# axiom_beta_sensor_cmv12000_tht_v0_16_r1_.net
KiCad netlist of a schematic drawn in EAGLE
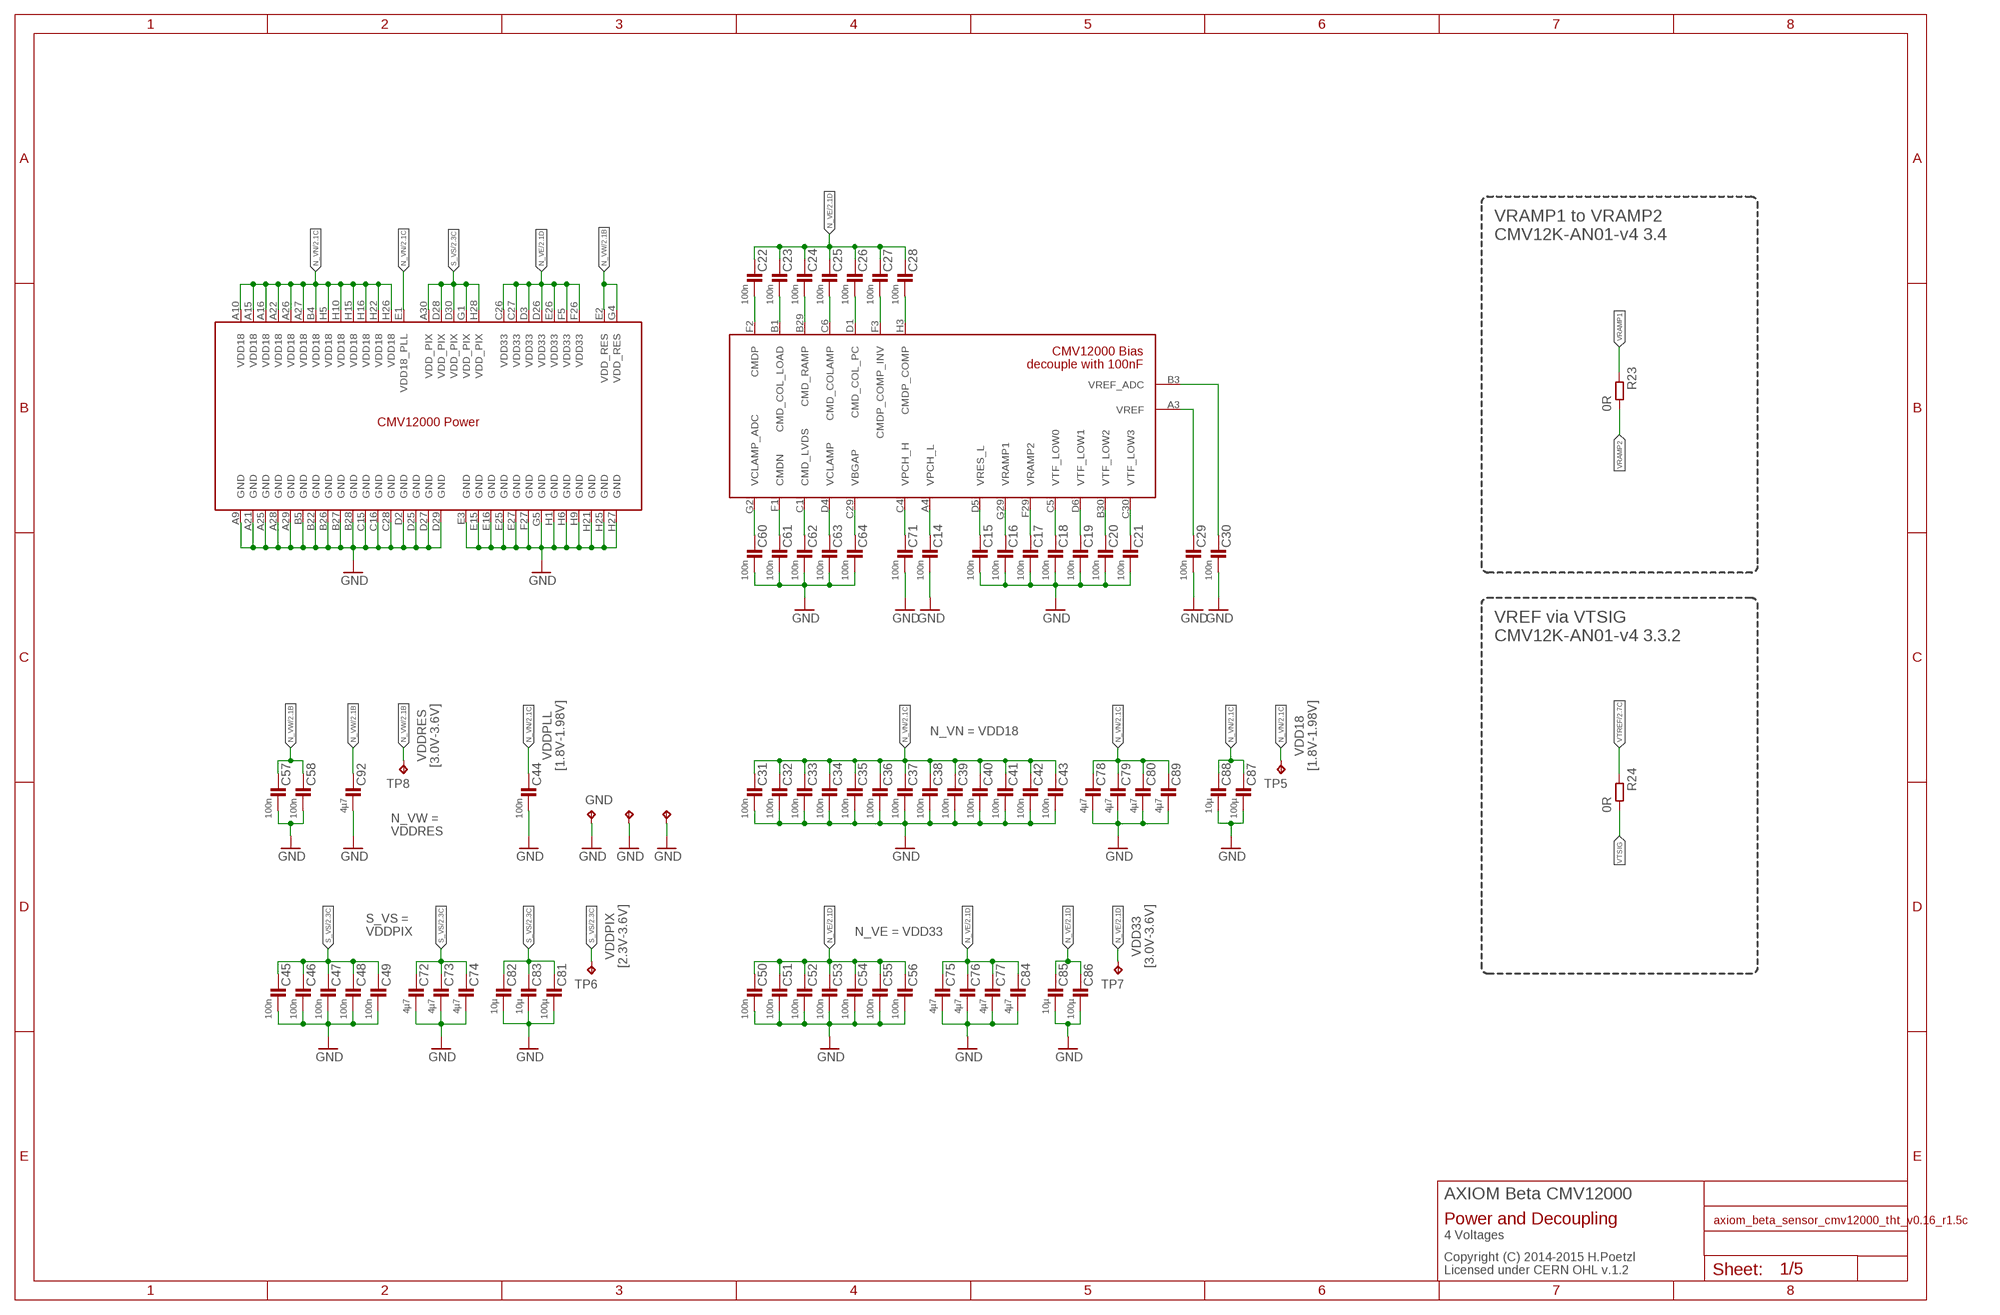
[diagram p0: schematic, sheet 1]
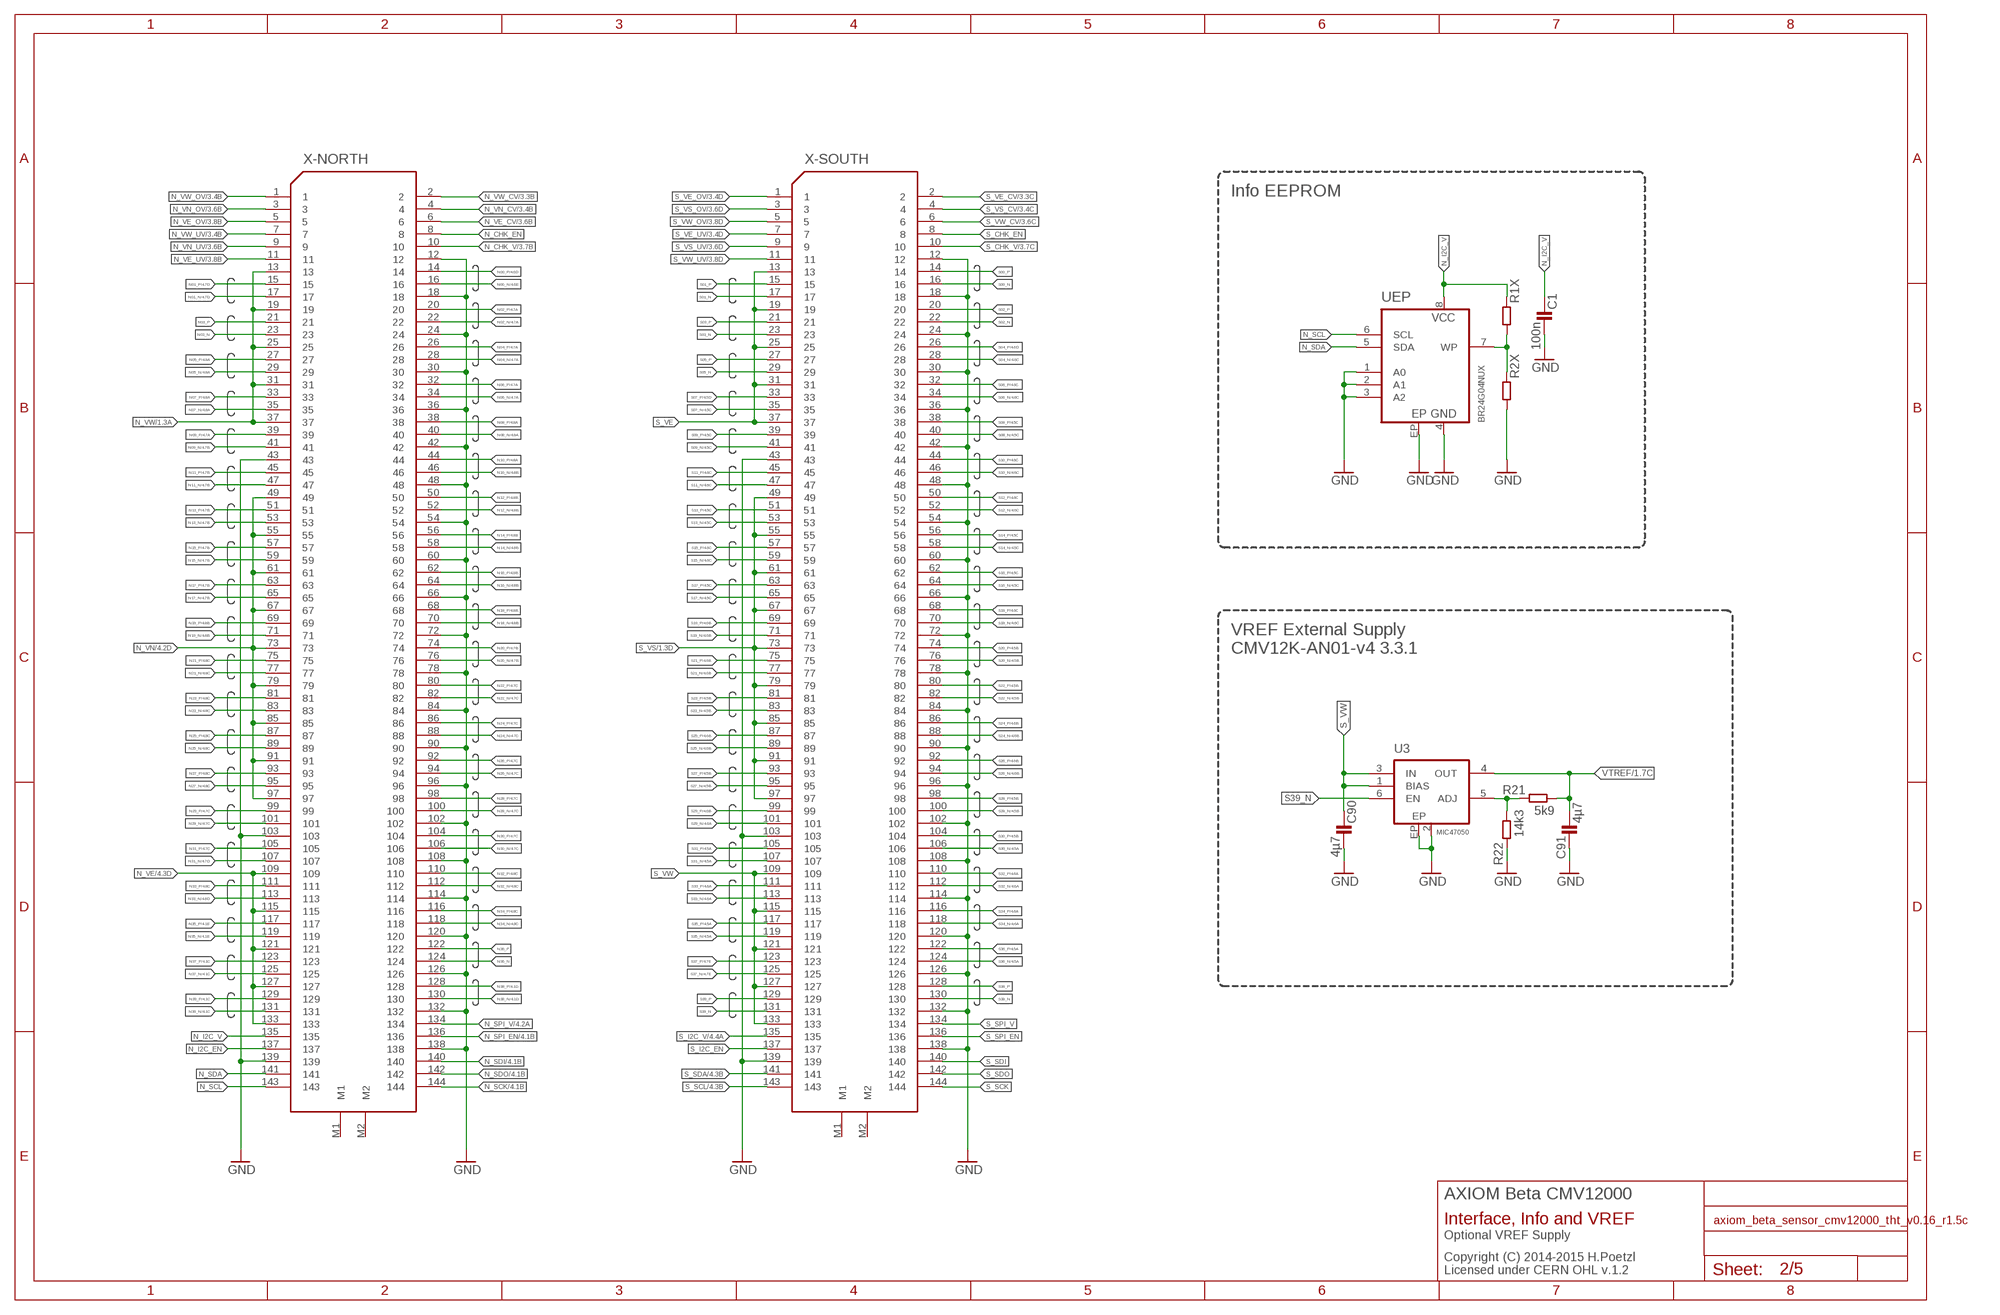
[diagram p1: schematic, sheet 2]
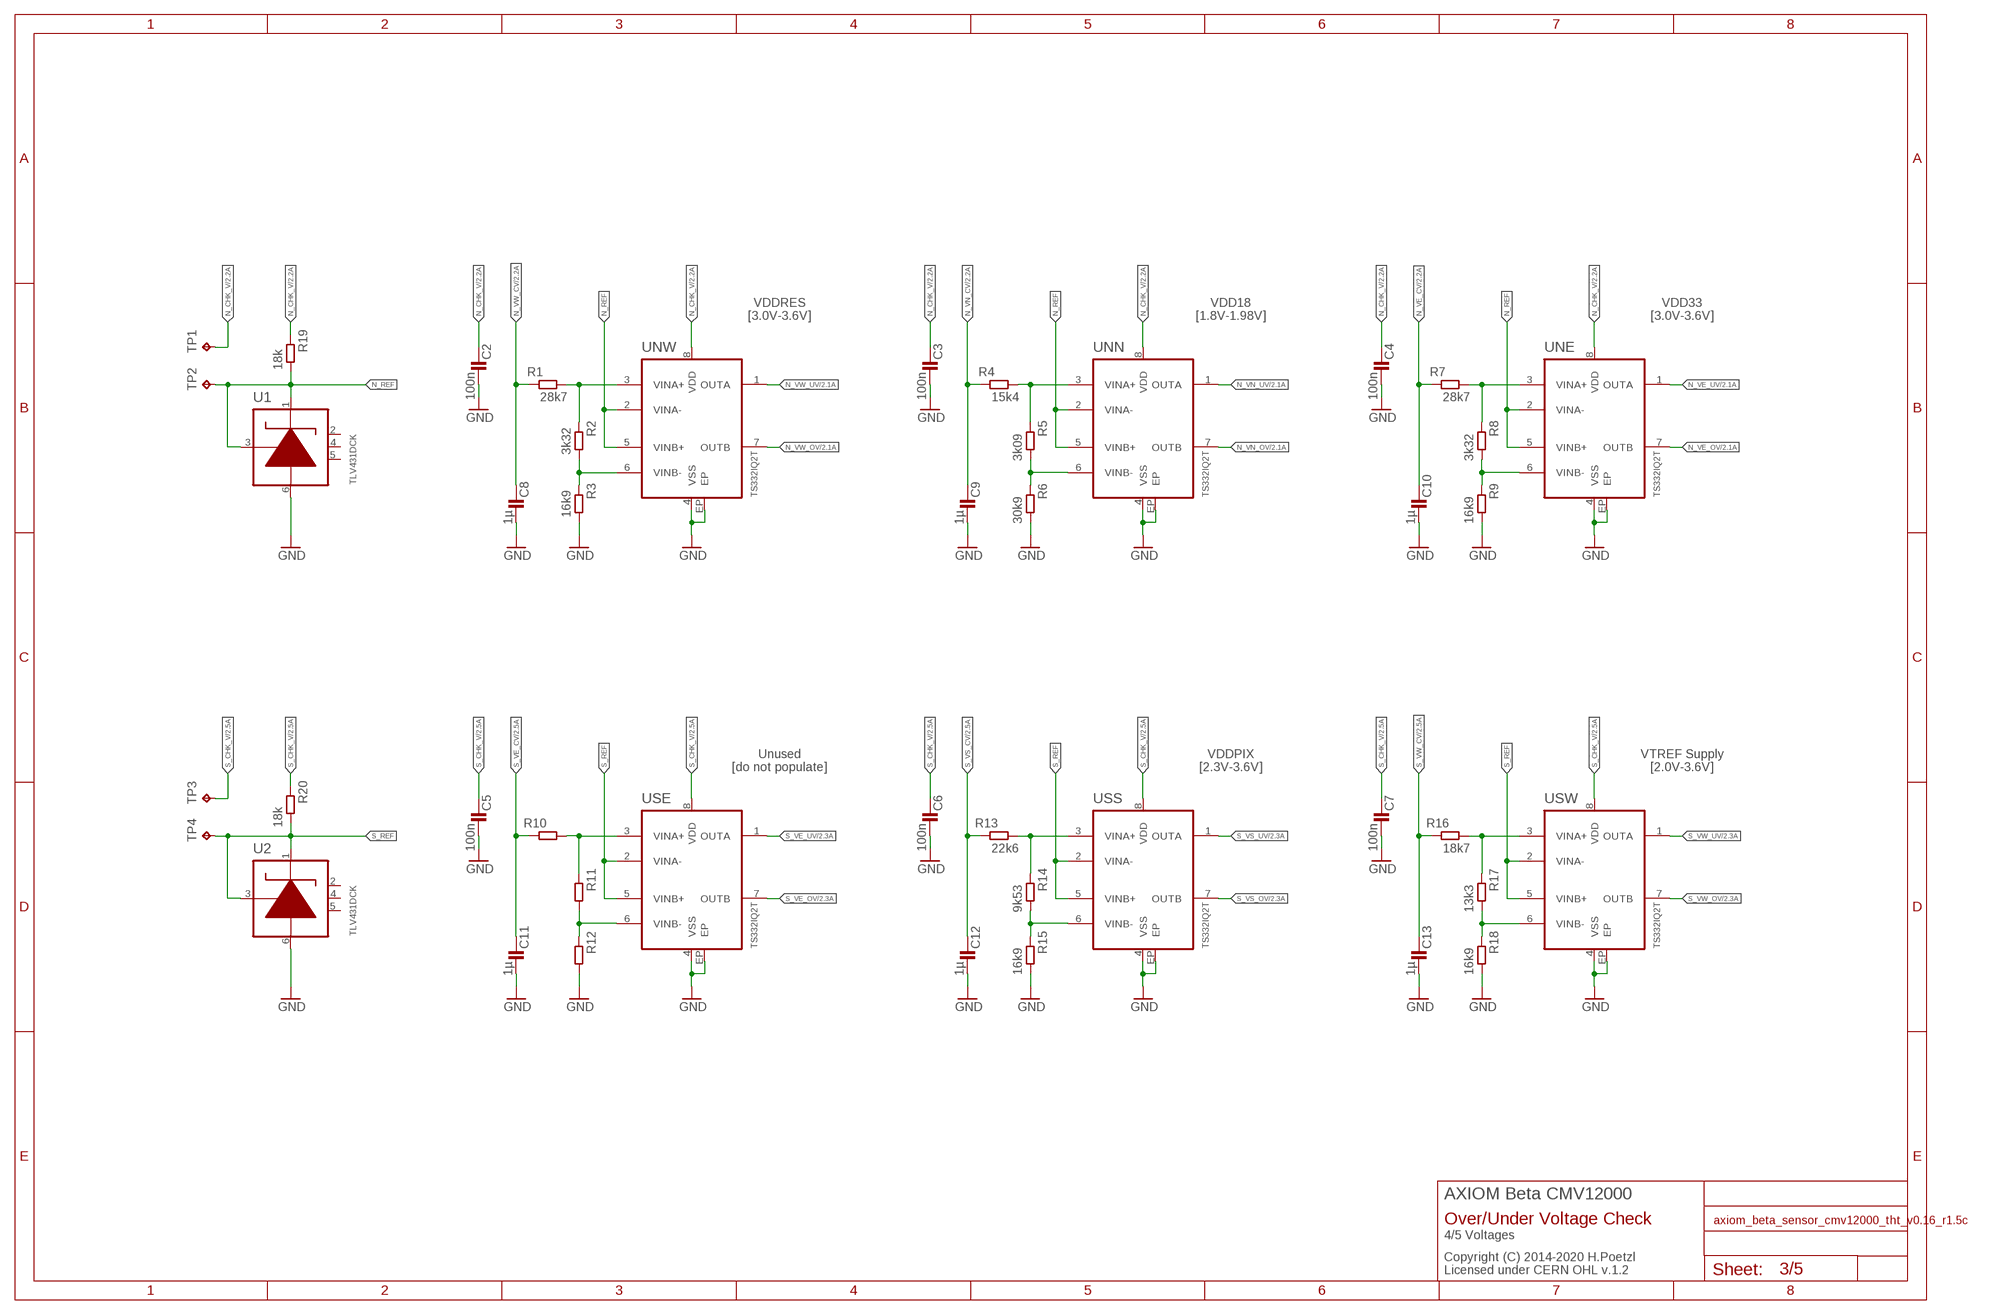
[diagram p2: schematic, sheet 3]
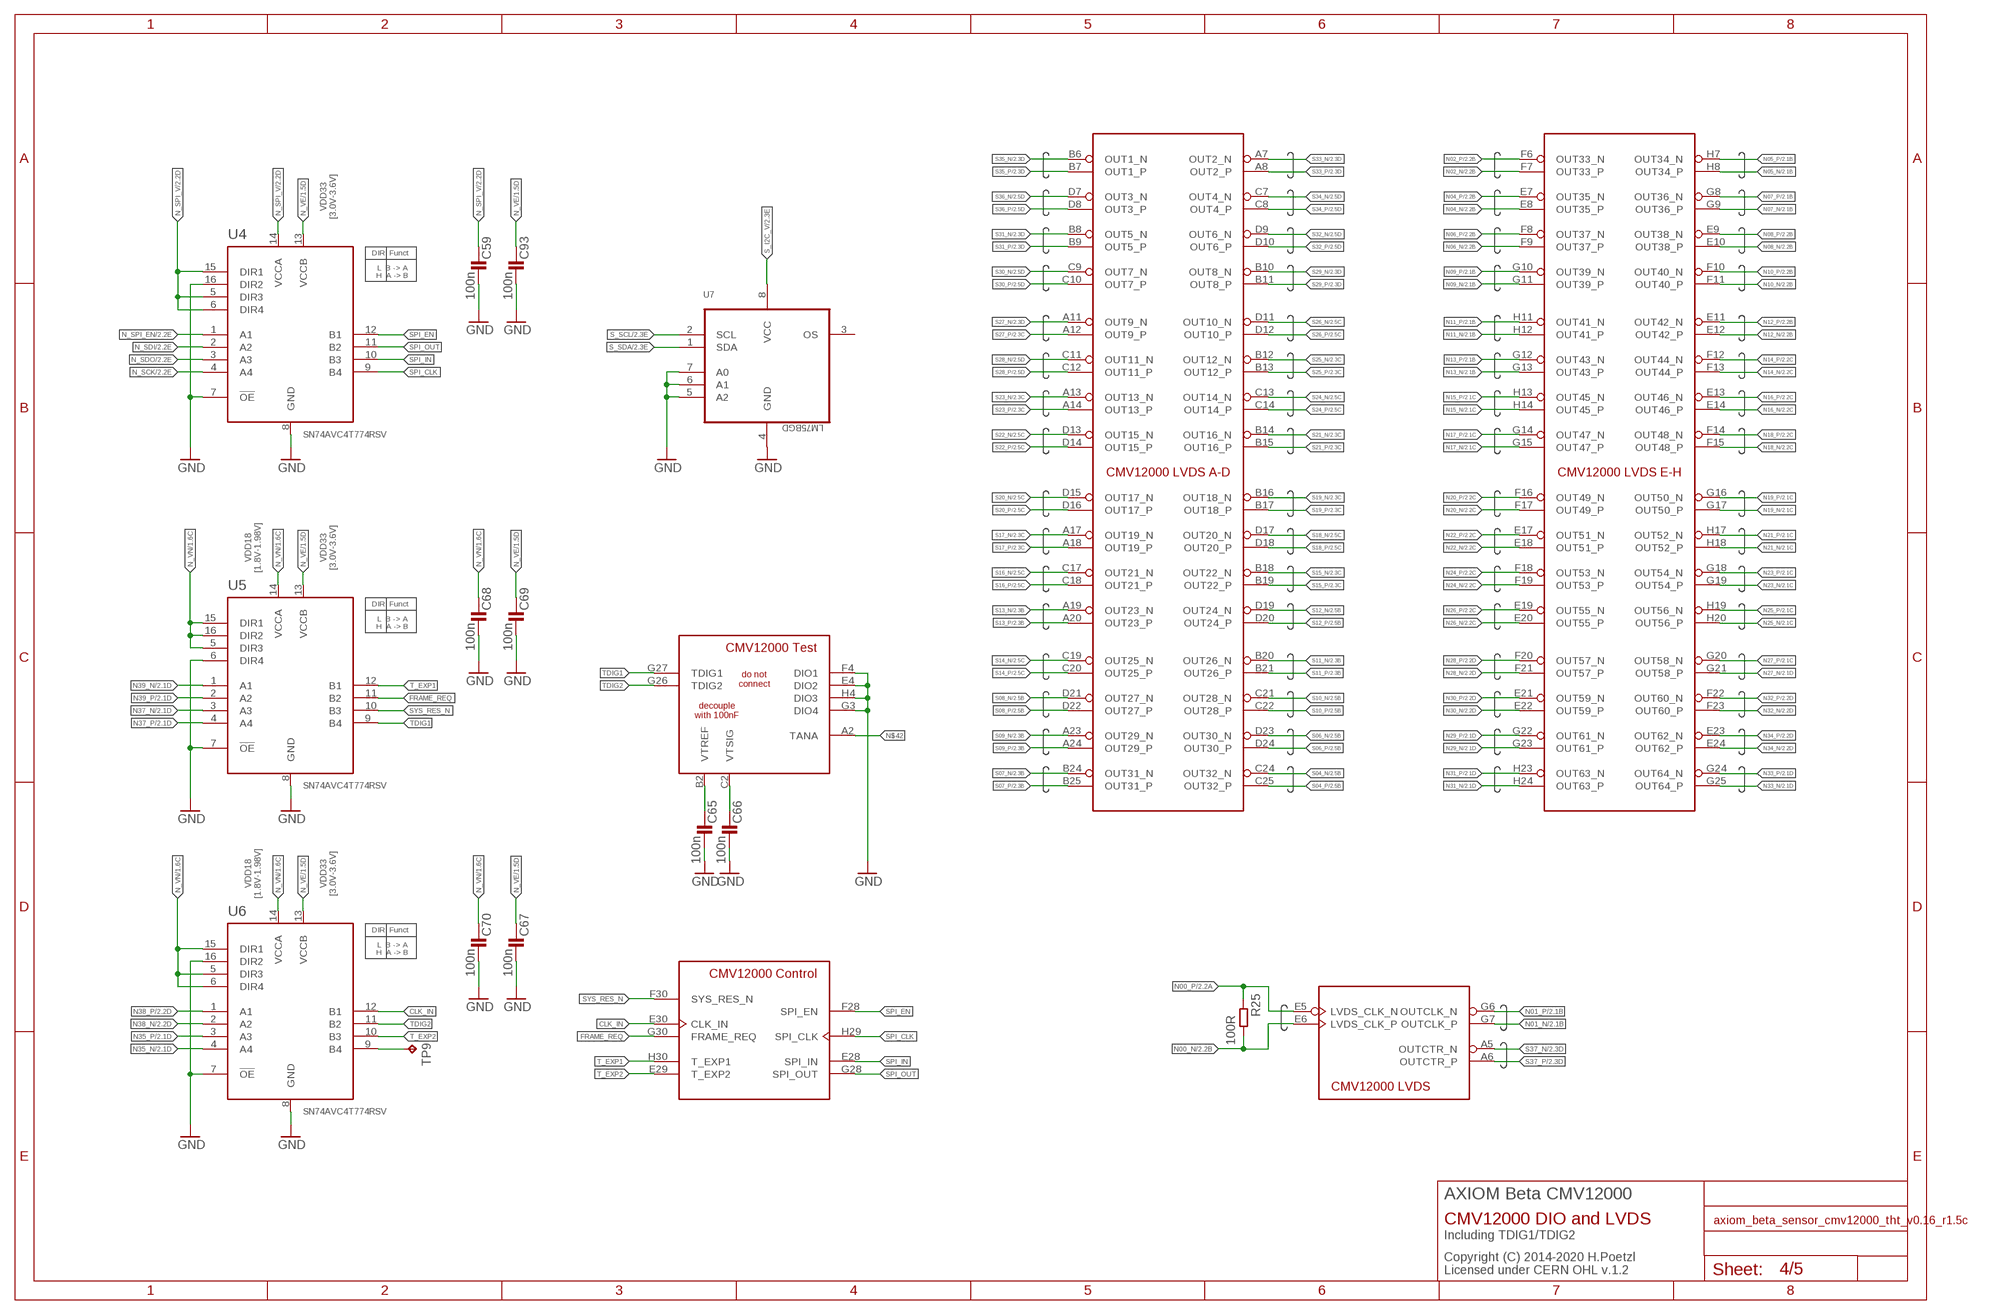
[diagram p3: schematic, sheet 4]
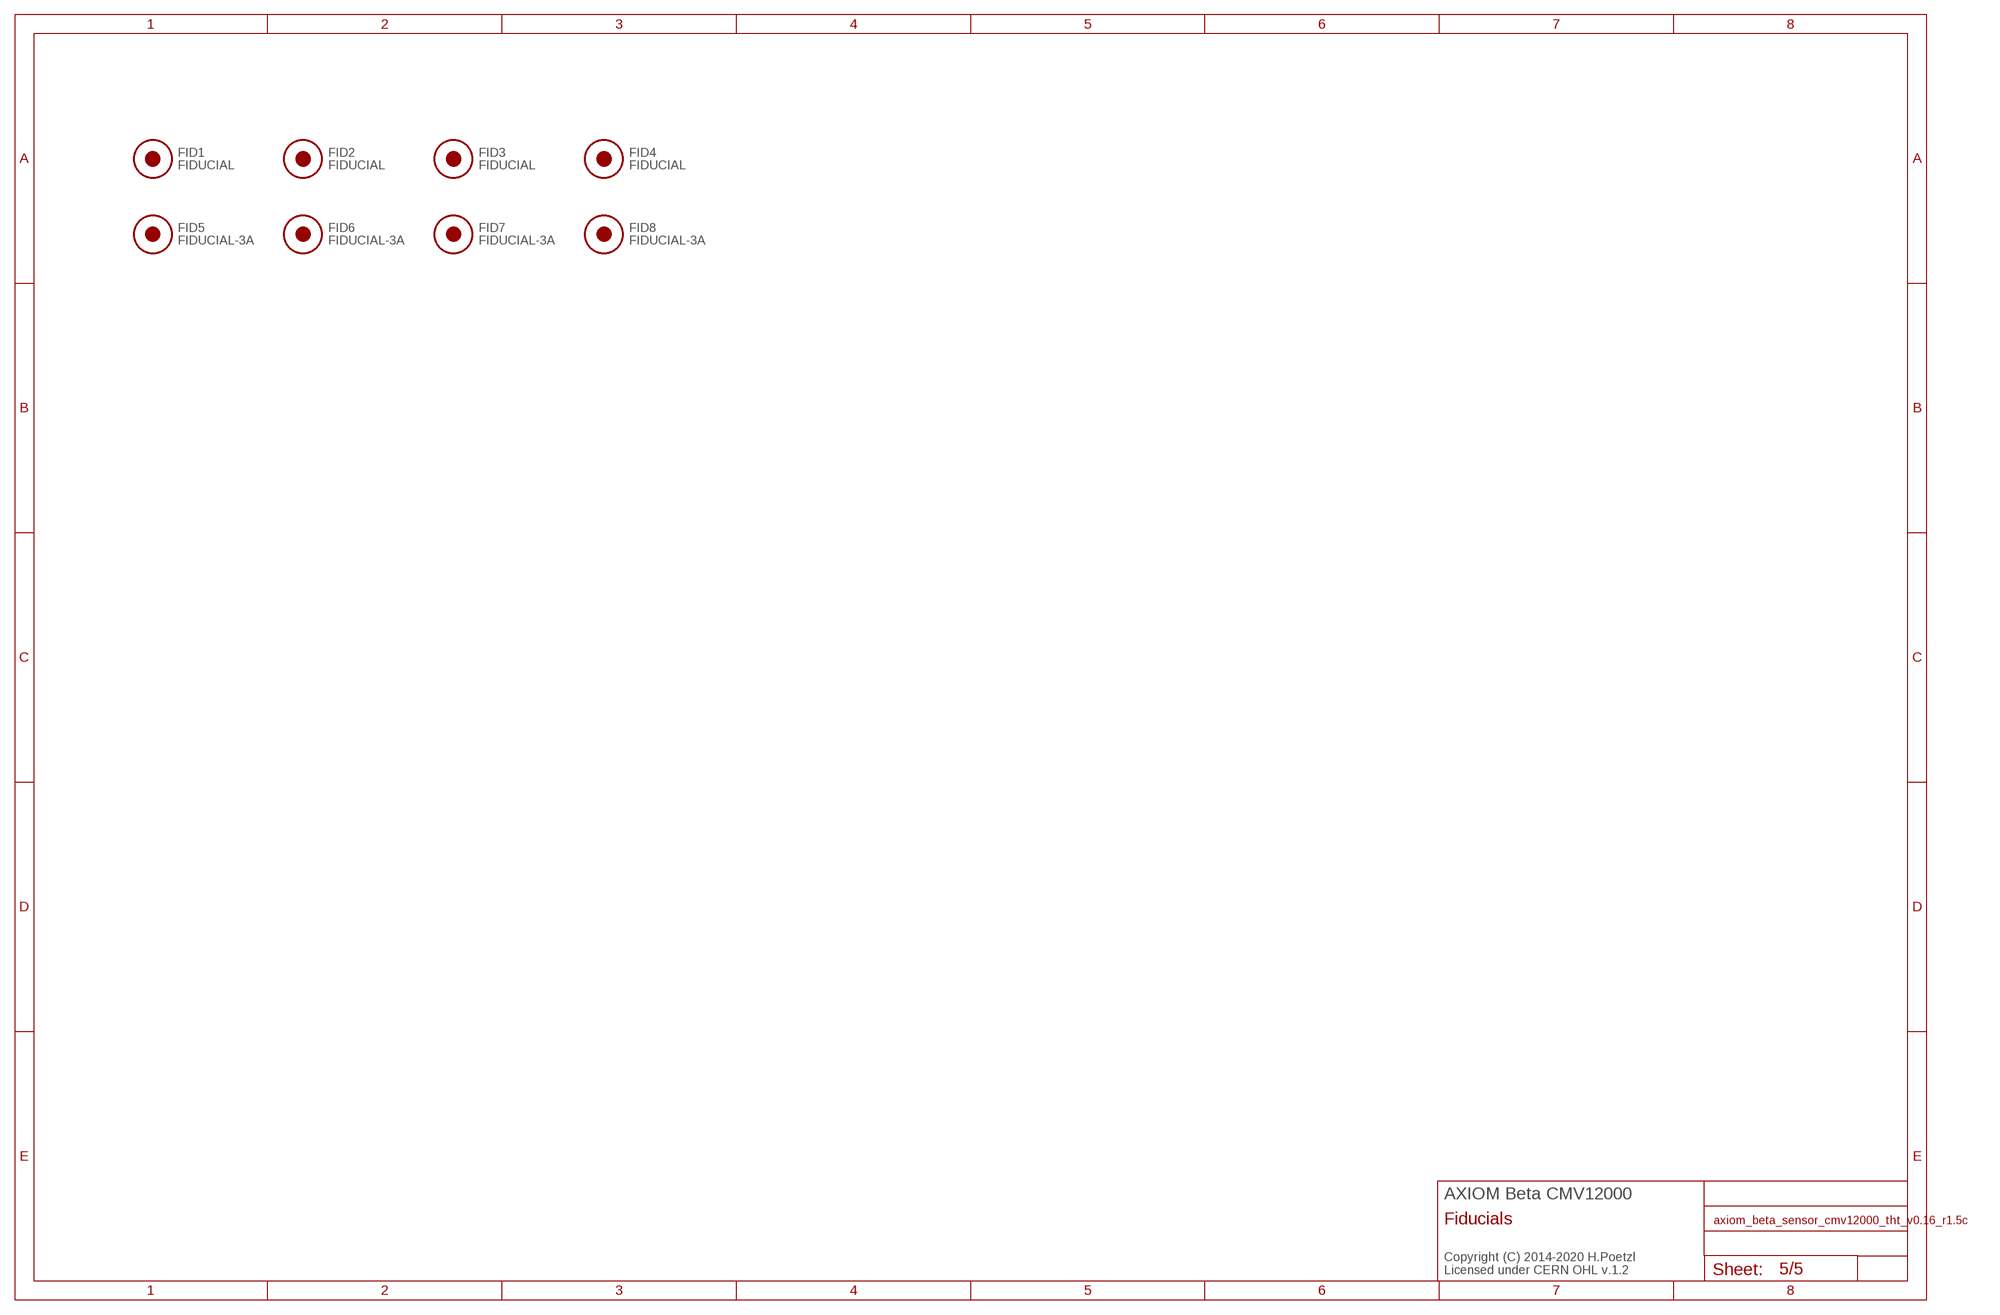
[diagram p4: schematic, sheet 5]

(export (version "E")
  (design (tool "Eeschema 10.0.6"))
  (components
    (comp (ref "FID1")
      (value "FIDUCIAL")
      (footprint "eagle-import:FID_ARROW")
      (libsource (lib "eagle-import") (part "FIDUCIAL"))
    )
    (comp (ref "FID2")
      (value "FIDUCIAL")
      (footprint "eagle-import:FID_ARROW")
      (libsource (lib "eagle-import") (part "FIDUCIAL"))
    )
    (comp (ref "FID3")
      (value "FIDUCIAL")
      (footprint "eagle-import:FID_ARROW")
      (libsource (lib "eagle-import") (part "FIDUCIAL"))
    )
    (comp (ref "FID4")
      (value "FIDUCIAL")
      (footprint "eagle-import:FID_ARROW")
      (libsource (lib "eagle-import") (part "FIDUCIAL"))
    )
    (comp (ref "FID5")
      (value "FIDUCIAL-3A")
      (footprint "eagle-import:FID_3ARROW")
      (libsource (lib "eagle-import") (part "FIDUCIAL-3A"))
    )
    (comp (ref "FID6")
      (value "FIDUCIAL-3A")
      (footprint "eagle-import:FID_3ARROW")
      (libsource (lib "eagle-import") (part "FIDUCIAL-3A"))
    )
    (comp (ref "FID7")
      (value "FIDUCIAL-3A")
      (footprint "eagle-import:FID_3ARROW")
      (libsource (lib "eagle-import") (part "FIDUCIAL-3A"))
    )
    (comp (ref "FID8")
      (value "FIDUCIAL-3A")
      (footprint "eagle-import:FID_3ARROW")
      (libsource (lib "eagle-import") (part "FIDUCIAL-3A"))
    )
    (comp (ref "C2")
      (value "100n")
      (footprint "eagle-import:0402-C")
      (libsource (lib "eagle-import") (part "C0402-C"))
    )
    (comp (ref "C3")
      (value "100n")
      (footprint "eagle-import:0402-C")
      (libsource (lib "eagle-import") (part "C0402-C"))
    )
    (comp (ref "C4")
      (value "100n")
      (footprint "eagle-import:0402-C")
      (libsource (lib "eagle-import") (part "C0402-C"))
    )
    (comp (ref "C5")
      (value "100n")
      (footprint "eagle-import:0402-C")
      (libsource (lib "eagle-import") (part "C0402-C"))
    )
    (comp (ref "C6")
      (value "100n")
      (footprint "eagle-import:0402-C")
      (libsource (lib "eagle-import") (part "C0402-C"))
    )
    (comp (ref "C7")
      (value "100n")
      (footprint "eagle-import:0402-C")
      (libsource (lib "eagle-import") (part "C0402-C"))
    )
    (comp (ref "C8")
      (value "1µ")
      (footprint "eagle-import:0402-C")
      (libsource (lib "eagle-import") (part "C0402-C"))
    )
    (comp (ref "C9")
      (value "1µ")
      (footprint "eagle-import:0402-C")
      (libsource (lib "eagle-import") (part "C0402-C"))
    )
    (comp (ref "C10")
      (value "1µ")
      (footprint "eagle-import:0402-C")
      (libsource (lib "eagle-import") (part "C0402-C"))
    )
    (comp (ref "C11")
      (value "1µ")
      (footprint "eagle-import:0402-C")
      (libsource (lib "eagle-import") (part "C0402-C"))
    )
    (comp (ref "C12")
      (value "1µ")
      (footprint "eagle-import:0402-C")
      (libsource (lib "eagle-import") (part "C0402-C"))
    )
    (comp (ref "C13")
      (value "1µ")
      (footprint "eagle-import:0402-C")
      (libsource (lib "eagle-import") (part "C0402-C"))
    )
    (comp (ref "R1")
      (value "28k7")
      (footprint "eagle-import:0402-C")
      (libsource (lib "eagle-import") (part "R0402-C"))
    )
    (comp (ref "R2")
      (value "3k32")
      (footprint "eagle-import:0402-C")
      (libsource (lib "eagle-import") (part "R0402-C"))
    )
    (comp (ref "R3")
      (value "16k9")
      (footprint "eagle-import:0402-C")
      (libsource (lib "eagle-import") (part "R0402-C"))
    )
    (comp (ref "R4")
      (value "15k4")
      (footprint "eagle-import:0402-C")
      (libsource (lib "eagle-import") (part "R0402-C"))
    )
    (comp (ref "R5")
      (value "3k09")
      (footprint "eagle-import:0402-C")
      (libsource (lib "eagle-import") (part "R0402-C"))
    )
    (comp (ref "R6")
      (value "30k9")
      (footprint "eagle-import:0402-C")
      (libsource (lib "eagle-import") (part "R0402-C"))
    )
    (comp (ref "R7")
      (value "28k7")
      (footprint "eagle-import:0402-C")
      (libsource (lib "eagle-import") (part "R0402-C"))
    )
    (comp (ref "R8")
      (value "3k32")
      (footprint "eagle-import:0402-C")
      (libsource (lib "eagle-import") (part "R0402-C"))
    )
    (comp (ref "R9")
      (value "16k9")
      (footprint "eagle-import:0402-C")
      (libsource (lib "eagle-import") (part "R0402-C"))
    )
    (comp (ref "R10")
      (value "R0402-C")
      (footprint "eagle-import:0402-C")
      (libsource (lib "eagle-import") (part "R0402-C"))
    )
    (comp (ref "R11")
      (value "R0402-C")
      (footprint "eagle-import:0402-C")
      (libsource (lib "eagle-import") (part "R0402-C"))
    )
    (comp (ref "R12")
      (value "R0402-C")
      (footprint "eagle-import:0402-C")
      (libsource (lib "eagle-import") (part "R0402-C"))
    )
    (comp (ref "R13")
      (value "22k6")
      (footprint "eagle-import:0402-C")
      (libsource (lib "eagle-import") (part "R0402-C"))
    )
    (comp (ref "R14")
      (value "9k53")
      (footprint "eagle-import:0402-C")
      (libsource (lib "eagle-import") (part "R0402-C"))
    )
    (comp (ref "R15")
      (value "16k9")
      (footprint "eagle-import:0402-C")
      (libsource (lib "eagle-import") (part "R0402-C"))
    )
    (comp (ref "R16")
      (value "18k7")
      (footprint "eagle-import:0402-C")
      (libsource (lib "eagle-import") (part "R0402-C"))
    )
    (comp (ref "R17")
      (value "13k3")
      (footprint "eagle-import:0402-C")
      (libsource (lib "eagle-import") (part "R0402-C"))
    )
    (comp (ref "R18")
      (value "16k9")
      (footprint "eagle-import:0402-C")
      (libsource (lib "eagle-import") (part "R0402-C"))
    )
    (comp (ref "R19")
      (value "18k")
      (footprint "eagle-import:0402-C")
      (libsource (lib "eagle-import") (part "R0402-C"))
    )
    (comp (ref "R20")
      (value "18k")
      (footprint "eagle-import:0402-C")
      (libsource (lib "eagle-import") (part "R0402-C"))
    )
    (comp (ref "TP1")
      (value "TPTP10R")
      (footprint "eagle-import:TP10R")
      (libsource (lib "eagle-import") (part "TPTP10R"))
    )
    (comp (ref "TP2")
      (value "TPTP10R")
      (footprint "eagle-import:TP10R")
      (libsource (lib "eagle-import") (part "TPTP10R"))
    )
    (comp (ref "TP3")
      (value "TPTP10R")
      (footprint "eagle-import:TP10R")
      (libsource (lib "eagle-import") (part "TPTP10R"))
    )
    (comp (ref "TP4")
      (value "TPTP10R")
      (footprint "eagle-import:TP10R")
      (libsource (lib "eagle-import") (part "TPTP10R"))
    )
    (comp (ref "U1")
      (value "TLV431DCK")
      (footprint "eagle-import:SOT65P210X110-6N")
      (libsource (lib "eagle-import") (part "TLV431DCK"))
    )
    (comp (ref "U2")
      (value "TLV431DCK")
      (footprint "eagle-import:SOT65P210X110-6N")
      (libsource (lib "eagle-import") (part "TLV431DCK"))
    )
    (comp (ref "UNE")
      (value "TS332IQ2T")
      (footprint "eagle-import:DFN200X200X100-9N")
      (libsource (lib "eagle-import") (part "TS332IQ2T"))
    )
    (comp (ref "UNN")
      (value "TS332IQ2T")
      (footprint "eagle-import:DFN200X200X100-9N")
      (libsource (lib "eagle-import") (part "TS332IQ2T"))
    )
    (comp (ref "UNW")
      (value "TS332IQ2T")
      (footprint "eagle-import:DFN200X200X100-9N")
      (libsource (lib "eagle-import") (part "TS332IQ2T"))
    )
    (comp (ref "USE")
      (value "TS332IQ2T")
      (footprint "eagle-import:DFN200X200X100-9N")
      (libsource (lib "eagle-import") (part "TS332IQ2T"))
    )
    (comp (ref "USS")
      (value "TS332IQ2T")
      (footprint "eagle-import:DFN200X200X100-9N")
      (libsource (lib "eagle-import") (part "TS332IQ2T"))
    )
    (comp (ref "USW")
      (value "TS332IQ2T")
      (footprint "eagle-import:DFN200X200X100-9N")
      (libsource (lib "eagle-import") (part "TS332IQ2T"))
    )
    (comp (ref "C1")
      (value "100n")
      (footprint "eagle-import:0402-C")
      (libsource (lib "eagle-import") (part "C0402-C"))
    )
    (comp (ref "C90")
      (value "4µ7")
      (footprint "eagle-import:0402-C")
      (libsource (lib "eagle-import") (part "C0402-C"))
    )
    (comp (ref "C91")
      (value "4µ7")
      (footprint "eagle-import:0402-C")
      (libsource (lib "eagle-import") (part "C0402-C"))
    )
    (comp (ref "R1X")
      (value "R0402-C")
      (footprint "eagle-import:0402-C")
      (libsource (lib "eagle-import") (part "R0402-C"))
    )
    (comp (ref "R2X")
      (value "R0402-C")
      (footprint "eagle-import:0402-C")
      (libsource (lib "eagle-import") (part "R0402-C"))
    )
    (comp (ref "R21")
      (value "5k9")
      (footprint "eagle-import:0402-C")
      (libsource (lib "eagle-import") (part "R0402-C"))
    )
    (comp (ref "R22")
      (value "14k3")
      (footprint "eagle-import:0402-C")
      (libsource (lib "eagle-import") (part "R0402-C"))
    )
    (comp (ref "U3")
      (value "MIC47050")
      (footprint "eagle-import:MLF-6")
      (libsource (lib "eagle-import") (part "MIC47050-ADJ"))
    )
    (comp (ref "UEP")
      (value "BR24G04NUX")
      (footprint "eagle-import:DFN200X300X100-9N")
      (libsource (lib "eagle-import") (part "BR24G04NUX"))
    )
    (comp (ref "X-NORTH")
      (value "FX10-144P")
      (footprint "eagle-import:FX10A-144P")
      (libsource (lib "eagle-import") (part "FX10-144P"))
    )
    (comp (ref "X-SOUTH")
      (value "FX10-144P")
      (footprint "eagle-import:FX10A-144P")
      (libsource (lib "eagle-import") (part "FX10-144P"))
    )
    (comp (ref "C14")
      (value "100n")
      (footprint "eagle-import:0402-C")
      (libsource (lib "eagle-import") (part "C0402-C"))
    )
    (comp (ref "C15")
      (value "100n")
      (footprint "eagle-import:0402-C")
      (libsource (lib "eagle-import") (part "C0402-C"))
    )
    (comp (ref "C16")
      (value "100n")
      (footprint "eagle-import:0402-C")
      (libsource (lib "eagle-import") (part "C0402-C"))
    )
    (comp (ref "C17")
      (value "100n")
      (footprint "eagle-import:0402-C")
      (libsource (lib "eagle-import") (part "C0402-C"))
    )
    (comp (ref "C18")
      (value "100n")
      (footprint "eagle-import:0402-C")
      (libsource (lib "eagle-import") (part "C0402-C"))
    )
    (comp (ref "C19")
      (value "100n")
      (footprint "eagle-import:0402-C")
      (libsource (lib "eagle-import") (part "C0402-C"))
    )
    (comp (ref "C20")
      (value "100n")
      (footprint "eagle-import:0402-C")
      (libsource (lib "eagle-import") (part "C0402-C"))
    )
    (comp (ref "C21")
      (value "100n")
      (footprint "eagle-import:0402-C")
      (libsource (lib "eagle-import") (part "C0402-C"))
    )
    (comp (ref "C22")
      (value "100n")
      (footprint "eagle-import:0402-C")
      (libsource (lib "eagle-import") (part "C0402-C"))
    )
    (comp (ref "C23")
      (value "100n")
      (footprint "eagle-import:0402-C")
      (libsource (lib "eagle-import") (part "C0402-C"))
    )
    (comp (ref "C24")
      (value "100n")
      (footprint "eagle-import:0402-C")
      (libsource (lib "eagle-import") (part "C0402-C"))
    )
    (comp (ref "C25")
      (value "100n")
      (footprint "eagle-import:0402-C")
      (libsource (lib "eagle-import") (part "C0402-C"))
    )
    (comp (ref "C26")
      (value "100n")
      (footprint "eagle-import:0402-C")
      (libsource (lib "eagle-import") (part "C0402-C"))
    )
    (comp (ref "C27")
      (value "100n")
      (footprint "eagle-import:0402-C")
      (libsource (lib "eagle-import") (part "C0402-C"))
    )
    (comp (ref "C28")
      (value "100n")
      (footprint "eagle-import:0402-C")
      (libsource (lib "eagle-import") (part "C0402-C"))
    )
    (comp (ref "C29")
      (value "100n")
      (footprint "eagle-import:0402-C")
      (libsource (lib "eagle-import") (part "C0402-C"))
    )
    (comp (ref "C30")
      (value "100n")
      (footprint "eagle-import:0402-C")
      (libsource (lib "eagle-import") (part "C0402-C"))
    )
    (comp (ref "C31")
      (value "100n")
      (footprint "eagle-import:0402-C")
      (libsource (lib "eagle-import") (part "C0402-C"))
    )
    (comp (ref "C32")
      (value "100n")
      (footprint "eagle-import:0402-C")
      (libsource (lib "eagle-import") (part "C0402-C"))
    )
    (comp (ref "C33")
      (value "100n")
      (footprint "eagle-import:0402-C")
      (libsource (lib "eagle-import") (part "C0402-C"))
    )
    (comp (ref "C34")
      (value "100n")
      (footprint "eagle-import:0402-C")
      (libsource (lib "eagle-import") (part "C0402-C"))
    )
    (comp (ref "C35")
      (value "100n")
      (footprint "eagle-import:0402-C")
      (libsource (lib "eagle-import") (part "C0402-C"))
    )
    (comp (ref "C36")
      (value "100n")
      (footprint "eagle-import:0402-C")
      (libsource (lib "eagle-import") (part "C0402-C"))
    )
    (comp (ref "C37")
      (value "100n")
      (footprint "eagle-import:0402-C")
      (libsource (lib "eagle-import") (part "C0402-C"))
    )
    (comp (ref "C38")
      (value "100n")
      (footprint "eagle-import:0402-C")
      (libsource (lib "eagle-import") (part "C0402-C"))
    )
    (comp (ref "C39")
      (value "100n")
      (footprint "eagle-import:0402-C")
      (libsource (lib "eagle-import") (part "C0402-C"))
    )
    (comp (ref "C40")
      (value "100n")
      (footprint "eagle-import:0402-C")
      (libsource (lib "eagle-import") (part "C0402-C"))
    )
    (comp (ref "C41")
      (value "100n")
      (footprint "eagle-import:0402-C")
      (libsource (lib "eagle-import") (part "C0402-C"))
    )
    (comp (ref "C42")
      (value "100n")
      (footprint "eagle-import:0402-C")
      (libsource (lib "eagle-import") (part "C0402-C"))
    )
    (comp (ref "C43")
      (value "100n")
      (footprint "eagle-import:0402-C")
      (libsource (lib "eagle-import") (part "C0402-C"))
    )
    (comp (ref "C44")
      (value "100n")
      (footprint "eagle-import:0402-C")
      (libsource (lib "eagle-import") (part "C0402-C"))
    )
    (comp (ref "C45")
      (value "100n")
      (footprint "eagle-import:0402-C")
      (libsource (lib "eagle-import") (part "C0402-C"))
    )
    (comp (ref "C46")
      (value "100n")
      (footprint "eagle-import:0402-C")
      (libsource (lib "eagle-import") (part "C0402-C"))
    )
    (comp (ref "C47")
      (value "100n")
      (footprint "eagle-import:0402-C")
      (libsource (lib "eagle-import") (part "C0402-C"))
    )
    (comp (ref "C48")
      (value "100n")
      (footprint "eagle-import:0402-C")
      (libsource (lib "eagle-import") (part "C0402-C"))
    )
    (comp (ref "C49")
      (value "100n")
      (footprint "eagle-import:0402-C")
      (libsource (lib "eagle-import") (part "C0402-C"))
    )
    (comp (ref "C50")
      (value "100n")
      (footprint "eagle-import:0402-C")
      (libsource (lib "eagle-import") (part "C0402-C"))
    )
    (comp (ref "C51")
      (value "100n")
      (footprint "eagle-import:0402-C")
      (libsource (lib "eagle-import") (part "C0402-C"))
    )
    (comp (ref "C52")
      (value "100n")
      (footprint "eagle-import:0402-C")
      (libsource (lib "eagle-import") (part "C0402-C"))
    )
    (comp (ref "C53")
      (value "100n")
      (footprint "eagle-import:0402-C")
      (libsource (lib "eagle-import") (part "C0402-C"))
    )
    (comp (ref "C54")
      (value "100n")
      (footprint "eagle-import:0402-C")
      (libsource (lib "eagle-import") (part "C0402-C"))
    )
    (comp (ref "C55")
      (value "100n")
      (footprint "eagle-import:0402-C")
      (libsource (lib "eagle-import") (part "C0402-C"))
    )
    (comp (ref "C56")
      (value "100n")
      (footprint "eagle-import:0402-C")
      (libsource (lib "eagle-import") (part "C0402-C"))
    )
    (comp (ref "C57")
      (value "100n")
      (footprint "eagle-import:0402-C")
      (libsource (lib "eagle-import") (part "C0402-C"))
    )
    (comp (ref "C58")
      (value "100n")
      (footprint "eagle-import:0402-C")
      (libsource (lib "eagle-import") (part "C0402-C"))
    )
    (comp (ref "C60")
      (value "100n")
      (footprint "eagle-import:0402-C")
      (libsource (lib "eagle-import") (part "C0402-C"))
    )
    (comp (ref "C61")
      (value "100n")
      (footprint "eagle-import:0402-C")
      (libsource (lib "eagle-import") (part "C0402-C"))
    )
    (comp (ref "C62")
      (value "100n")
      (footprint "eagle-import:0402-C")
      (libsource (lib "eagle-import") (part "C0402-C"))
    )
    (comp (ref "C63")
      (value "100n")
      (footprint "eagle-import:0402-C")
      (libsource (lib "eagle-import") (part "C0402-C"))
    )
    (comp (ref "C64")
      (value "100n")
      (footprint "eagle-import:0402-C")
      (libsource (lib "eagle-import") (part "C0402-C"))
    )
    (comp (ref "C71")
      (value "100n")
      (footprint "eagle-import:0402-C")
      (libsource (lib "eagle-import") (part "C0402-C"))
    )
    (comp (ref "C72")
      (value "4µ7")
      (footprint "eagle-import:0402-B")
      (libsource (lib "eagle-import") (part "C0402-B"))
    )
    (comp (ref "C73")
      (value "4µ7")
      (footprint "eagle-import:0402-C")
      (libsource (lib "eagle-import") (part "C0402-C"))
    )
    (comp (ref "C74")
      (value "4µ7")
      (footprint "eagle-import:0402-C")
      (libsource (lib "eagle-import") (part "C0402-C"))
    )
    (comp (ref "C75")
      (value "4µ7")
      (footprint "eagle-import:0402-C")
      (libsource (lib "eagle-import") (part "C0402-C"))
    )
    (comp (ref "C76")
      (value "4µ7")
      (footprint "eagle-import:0402-C")
      (libsource (lib "eagle-import") (part "C0402-C"))
    )
    (comp (ref "C77")
      (value "4µ7")
      (footprint "eagle-import:0402-B")
      (libsource (lib "eagle-import") (part "C0402-B"))
    )
    (comp (ref "C78")
      (value "4µ7")
      (footprint "eagle-import:0402-B")
      (libsource (lib "eagle-import") (part "C0402-B"))
    )
    (comp (ref "C79")
      (value "4µ7")
      (footprint "eagle-import:0402-C")
      (libsource (lib "eagle-import") (part "C0402-C"))
    )
    (comp (ref "C80")
      (value "4µ7")
      (footprint "eagle-import:0402-C")
      (libsource (lib "eagle-import") (part "C0402-C"))
    )
    (comp (ref "C81")
      (value "100µ")
      (footprint "eagle-import:1206-B")
      (libsource (lib "eagle-import") (part "C1206-B"))
    )
    (comp (ref "C82")
      (value "10µ")
      (footprint "eagle-import:0603-C")
      (libsource (lib "eagle-import") (part "C0603-C"))
    )
    (comp (ref "C83")
      (value "10µ")
      (footprint "eagle-import:0603-C")
      (libsource (lib "eagle-import") (part "C0603-C"))
    )
    (comp (ref "C84")
      (value "4µ7")
      (footprint "eagle-import:0402-C")
      (libsource (lib "eagle-import") (part "C0402-C"))
    )
    (comp (ref "C85")
      (value "10µ")
      (footprint "eagle-import:0603-C")
      (libsource (lib "eagle-import") (part "C0603-C"))
    )
    (comp (ref "C86")
      (value "100µ")
      (footprint "eagle-import:1206-B")
      (libsource (lib "eagle-import") (part "C1206-B"))
    )
    (comp (ref "C87")
      (value "100µ")
      (footprint "eagle-import:1206-B")
      (libsource (lib "eagle-import") (part "C1206-B"))
    )
    (comp (ref "C88")
      (value "10µ")
      (footprint "eagle-import:0603-C")
      (libsource (lib "eagle-import") (part "C0603-C"))
    )
    (comp (ref "C89")
      (value "4µ7")
      (footprint "eagle-import:0402-C")
      (libsource (lib "eagle-import") (part "C0402-C"))
    )
    (comp (ref "C92")
      (value "4µ7")
      (footprint "eagle-import:0402-C")
      (libsource (lib "eagle-import") (part "C0402-C"))
    )
    (comp (ref "GND")
      (value "TPTP10R")
      (footprint "eagle-import:TP10R")
      (libsource (lib "eagle-import") (part "TPTP10R"))
    )
    (comp (ref "GND75")
      (value "TPTP10R")
      (footprint "eagle-import:TP10R")
      (libsource (lib "eagle-import") (part "TPTP10R"))
    )
    (comp (ref "GND77")
      (value "TPTP10R")
      (footprint "eagle-import:TP10R")
      (libsource (lib "eagle-import") (part "TPTP10R"))
    )
    (comp (ref "R23")
      (value "0R")
      (footprint "eagle-import:0402-C")
      (libsource (lib "eagle-import") (part "R0402-C"))
    )
    (comp (ref "R24")
      (value "0R")
      (footprint "eagle-import:0402-C")
      (libsource (lib "eagle-import") (part "R0402-C"))
    )
    (comp (ref "SENSOR")
      (value "CMV12000ANDON")
      (footprint "eagle-import:10-30-07-237-400T4")
      (libsource (lib "eagle-import") (part "CMV12000ANDON"))
    )
    (comp (ref "TP5")
      (value "TPTP10R")
      (footprint "eagle-import:TP10R")
      (libsource (lib "eagle-import") (part "TPTP10R"))
    )
    (comp (ref "TP6")
      (value "TPTP10R")
      (footprint "eagle-import:TP10R")
      (libsource (lib "eagle-import") (part "TPTP10R"))
    )
    (comp (ref "TP7")
      (value "TPTP10R")
      (footprint "eagle-import:TP10R")
      (libsource (lib "eagle-import") (part "TPTP10R"))
    )
    (comp (ref "TP8")
      (value "TPTP10R")
      (footprint "eagle-import:TP10R")
      (libsource (lib "eagle-import") (part "TPTP10R"))
    )
    (comp (ref "C59")
      (value "100n")
      (footprint "eagle-import:0402-C")
      (libsource (lib "eagle-import") (part "C0402-C"))
    )
    (comp (ref "C65")
      (value "100n")
      (footprint "eagle-import:0402-C")
      (libsource (lib "eagle-import") (part "C0402-C"))
    )
    (comp (ref "C66")
      (value "100n")
      (footprint "eagle-import:0402-C")
      (libsource (lib "eagle-import") (part "C0402-C"))
    )
    (comp (ref "C67")
      (value "100n")
      (footprint "eagle-import:0402-C")
      (libsource (lib "eagle-import") (part "C0402-C"))
    )
    (comp (ref "C68")
      (value "100n")
      (footprint "eagle-import:0402-C")
      (libsource (lib "eagle-import") (part "C0402-C"))
    )
    (comp (ref "C69")
      (value "100n")
      (footprint "eagle-import:0402-C")
      (libsource (lib "eagle-import") (part "C0402-C"))
    )
    (comp (ref "C70")
      (value "100n")
      (footprint "eagle-import:0402-C")
      (libsource (lib "eagle-import") (part "C0402-C"))
    )
    (comp (ref "C93")
      (value "100n")
      (footprint "eagle-import:0402-C")
      (libsource (lib "eagle-import") (part "C0402-C"))
    )
    (comp (ref "R25")
      (value "100R")
      (footprint "eagle-import:0402-C")
      (libsource (lib "eagle-import") (part "R0402-C"))
    )
    (comp (ref "TP9")
      (value "TPTP10R")
      (footprint "eagle-import:TP10R")
      (libsource (lib "eagle-import") (part "TPTP10R"))
    )
    (comp (ref "U4")
      (value "SN74AVC4T774RSV")
      (footprint "eagle-import:QFN40P185X265X55-16N")
      (libsource (lib "eagle-import") (part "SN74AVC4T774RSV"))
    )
    (comp (ref "U5")
      (value "SN74AVC4T774RSV")
      (footprint "eagle-import:QFN40P185X265X55-16N")
      (libsource (lib "eagle-import") (part "SN74AVC4T774RSV"))
    )
    (comp (ref "U6")
      (value "SN74AVC4T774RSV")
      (footprint "eagle-import:QFN40P185X265X55-16N")
      (libsource (lib "eagle-import") (part "SN74AVC4T774RSV"))
    )
    (comp (ref "U7")
      (value "LM75BGD")
      (footprint "eagle-import:SOT996-2_3")
      (libsource (lib "eagle-import") (part "LM75BGD"))
    )
  )
  (nets
    (net (code "1") (name "CLK_IN") (class "Default")
      (node (ref "SENSOR") (pin "E30") (pinfunction "CLK_IN_E30") (pintype "input"))
      (node (ref "U6") (pin "12") (pinfunction "B1_12") (pintype "bidirectional"))
    )
    (net (code "2") (name "FRAME_REQ") (class "Default")
      (node (ref "SENSOR") (pin "G30") (pinfunction "FRAME_REQ_G30") (pintype "input"))
      (node (ref "U5") (pin "11") (pinfunction "B2_11") (pintype "bidirectional"))
    )
    (net (code "3") (name "GND") (class "Default")
      (node (ref "C1") (pin "2") (pinfunction "2_2") (pintype "passive"))
      (node (ref "C10") (pin "2") (pinfunction "2_2") (pintype "passive"))
      (node (ref "C11") (pin "2") (pinfunction "2_2") (pintype "passive"))
      (node (ref "C12") (pin "2") (pinfunction "2_2") (pintype "passive"))
      (node (ref "C13") (pin "2") (pinfunction "2_2") (pintype "passive"))
      (node (ref "C14") (pin "2") (pinfunction "2_2") (pintype "passive"))
      (node (ref "C15") (pin "2") (pinfunction "2_2") (pintype "passive"))
      (node (ref "C16") (pin "2") (pinfunction "2_2") (pintype "passive"))
      (node (ref "C17") (pin "2") (pinfunction "2_2") (pintype "passive"))
      (node (ref "C18") (pin "2") (pinfunction "2_2") (pintype "passive"))
      (node (ref "C19") (pin "2") (pinfunction "2_2") (pintype "passive"))
      (node (ref "C2") (pin "2") (pinfunction "2_2") (pintype "passive"))
      (node (ref "C20") (pin "2") (pinfunction "2_2") (pintype "passive"))
      (node (ref "C21") (pin "2") (pinfunction "2_2") (pintype "passive"))
      (node (ref "C29") (pin "2") (pinfunction "2_2") (pintype "passive"))
      (node (ref "C3") (pin "2") (pinfunction "2_2") (pintype "passive"))
      (node (ref "C30") (pin "2") (pinfunction "2_2") (pintype "passive"))
      (node (ref "C31") (pin "2") (pinfunction "2_2") (pintype "passive"))
      (node (ref "C32") (pin "2") (pinfunction "2_2") (pintype "passive"))
      (node (ref "C33") (pin "2") (pinfunction "2_2") (pintype "passive"))
      (node (ref "C34") (pin "2") (pinfunction "2_2") (pintype "passive"))
      (node (ref "C35") (pin "2") (pinfunction "2_2") (pintype "passive"))
      (node (ref "C36") (pin "2") (pinfunction "2_2") (pintype "passive"))
      (node (ref "C37") (pin "2") (pinfunction "2_2") (pintype "passive"))
      (node (ref "C38") (pin "2") (pinfunction "2_2") (pintype "passive"))
      (node (ref "C39") (pin "2") (pinfunction "2_2") (pintype "passive"))
      (node (ref "C4") (pin "2") (pinfunction "2_2") (pintype "passive"))
      (node (ref "C40") (pin "2") (pinfunction "2_2") (pintype "passive"))
      (node (ref "C41") (pin "2") (pinfunction "2_2") (pintype "passive"))
      (node (ref "C42") (pin "2") (pinfunction "2_2") (pintype "passive"))
      (node (ref "C43") (pin "2") (pinfunction "2_2") (pintype "passive"))
      (node (ref "C44") (pin "2") (pinfunction "2_2") (pintype "passive"))
      (node (ref "C45") (pin "2") (pinfunction "2_2") (pintype "passive"))
      (node (ref "C46") (pin "2") (pinfunction "2_2") (pintype "passive"))
      (node (ref "C47") (pin "2") (pinfunction "2_2") (pintype "passive"))
      (node (ref "C48") (pin "2") (pinfunction "2_2") (pintype "passive"))
      (node (ref "C49") (pin "2") (pinfunction "2_2") (pintype "passive"))
      (node (ref "C5") (pin "2") (pinfunction "2_2") (pintype "passive"))
      (node (ref "C50") (pin "2") (pinfunction "2_2") (pintype "passive"))
      (node (ref "C51") (pin "2") (pinfunction "2_2") (pintype "passive"))
      (node (ref "C52") (pin "2") (pinfunction "2_2") (pintype "passive"))
      (node (ref "C53") (pin "2") (pinfunction "2_2") (pintype "passive"))
      (node (ref "C54") (pin "2") (pinfunction "2_2") (pintype "passive"))
      (node (ref "C55") (pin "2") (pinfunction "2_2") (pintype "passive"))
      (node (ref "C56") (pin "2") (pinfunction "2_2") (pintype "passive"))
      (node (ref "C57") (pin "2") (pinfunction "2_2") (pintype "passive"))
      (node (ref "C58") (pin "2") (pinfunction "2_2") (pintype "passive"))
      (node (ref "C59") (pin "2") (pinfunction "2_2") (pintype "passive"))
      (node (ref "C6") (pin "2") (pinfunction "2_2") (pintype "passive"))
      (node (ref "C60") (pin "2") (pinfunction "2_2") (pintype "passive"))
      (node (ref "C61") (pin "2") (pinfunction "2_2") (pintype "passive"))
      (node (ref "C62") (pin "2") (pinfunction "2_2") (pintype "passive"))
      (node (ref "C63") (pin "2") (pinfunction "2_2") (pintype "passive"))
      (node (ref "C64") (pin "2") (pinfunction "2_2") (pintype "passive"))
      (node (ref "C65") (pin "2") (pinfunction "2_2") (pintype "passive"))
      (node (ref "C66") (pin "2") (pinfunction "2_2") (pintype "passive"))
      (node (ref "C67") (pin "2") (pinfunction "2_2") (pintype "passive"))
      (node (ref "C68") (pin "2") (pinfunction "2_2") (pintype "passive"))
      (node (ref "C69") (pin "2") (pinfunction "2_2") (pintype "passive"))
      (node (ref "C7") (pin "2") (pinfunction "2_2") (pintype "passive"))
      (node (ref "C70") (pin "2") (pinfunction "2_2") (pintype "passive"))
      (node (ref "C71") (pin "2") (pinfunction "2_2") (pintype "passive"))
      (node (ref "C72") (pin "2") (pinfunction "2_2") (pintype "passive"))
      (node (ref "C73") (pin "2") (pinfunction "2_2") (pintype "passive"))
      (node (ref "C74") (pin "2") (pinfunction "2_2") (pintype "passive"))
      (node (ref "C75") (pin "2") (pinfunction "2_2") (pintype "passive"))
      (node (ref "C76") (pin "2") (pinfunction "2_2") (pintype "passive"))
      (node (ref "C77") (pin "2") (pinfunction "2_2") (pintype "passive"))
      (node (ref "C78") (pin "2") (pinfunction "2_2") (pintype "passive"))
      (node (ref "C79") (pin "2") (pinfunction "2_2") (pintype "passive"))
      (node (ref "C8") (pin "2") (pinfunction "2_2") (pintype "passive"))
      (node (ref "C80") (pin "2") (pinfunction "2_2") (pintype "passive"))
      (node (ref "C81") (pin "2") (pinfunction "2_2") (pintype "passive"))
      (node (ref "C82") (pin "2") (pinfunction "2_2") (pintype "passive"))
      (node (ref "C83") (pin "2") (pinfunction "2_2") (pintype "passive"))
      (node (ref "C84") (pin "2") (pinfunction "2_2") (pintype "passive"))
      (node (ref "C85") (pin "2") (pinfunction "2_2") (pintype "passive"))
      (node (ref "C86") (pin "2") (pinfunction "2_2") (pintype "passive"))
      (node (ref "C87") (pin "2") (pinfunction "2_2") (pintype "passive"))
      (node (ref "C88") (pin "2") (pinfunction "2_2") (pintype "passive"))
      (node (ref "C89") (pin "2") (pinfunction "2_2") (pintype "passive"))
      (node (ref "C9") (pin "2") (pinfunction "2_2") (pintype "passive"))
      (node (ref "C90") (pin "2") (pinfunction "2_2") (pintype "passive"))
      (node (ref "C91") (pin "1") (pinfunction "1_1") (pintype "passive"))
      (node (ref "C92") (pin "2") (pinfunction "2_2") (pintype "passive"))
      (node (ref "C93") (pin "2") (pinfunction "2_2") (pintype "passive"))
      (node (ref "GND") (pin "TP") (pinfunction "TP_TP") (pintype "input"))
      (node (ref "GND75") (pin "TP") (pinfunction "TP_TP") (pintype "input"))
      (node (ref "GND77") (pin "TP") (pinfunction "TP_TP") (pintype "input"))
      (node (ref "R12") (pin "2") (pinfunction "2_2") (pintype "passive"))
      (node (ref "R15") (pin "2") (pinfunction "2_2") (pintype "passive"))
      (node (ref "R18") (pin "2") (pinfunction "2_2") (pintype "passive"))
      (node (ref "R22") (pin "1") (pinfunction "1_1") (pintype "passive"))
      (node (ref "R2X") (pin "2") (pinfunction "2_2") (pintype "passive"))
      (node (ref "R3") (pin "2") (pinfunction "2_2") (pintype "passive"))
      (node (ref "R6") (pin "2") (pinfunction "2_2") (pintype "passive"))
      (node (ref "R9") (pin "2") (pinfunction "2_2") (pintype "passive"))
      (node (ref "SENSOR") (pin "A21") (pinfunction "GND_A21") (pintype "power_in"))
      (node (ref "SENSOR") (pin "A25") (pinfunction "GND_A25") (pintype "power_in"))
      (node (ref "SENSOR") (pin "A28") (pinfunction "GND_A28") (pintype "power_in"))
      (node (ref "SENSOR") (pin "A29") (pinfunction "GND_A29") (pintype "power_in"))
      (node (ref "SENSOR") (pin "A9") (pinfunction "GND_A9") (pintype "power_in"))
      (node (ref "SENSOR") (pin "B22") (pinfunction "GND_B22") (pintype "power_in"))
      (node (ref "SENSOR") (pin "B26") (pinfunction "GND_B26") (pintype "power_in"))
      (node (ref "SENSOR") (pin "B27") (pinfunction "GND_B27") (pintype "power_in"))
      (node (ref "SENSOR") (pin "B28") (pinfunction "GND_B28") (pintype "power_in"))
      (node (ref "SENSOR") (pin "B5") (pinfunction "GND_B5") (pintype "power_in"))
      (node (ref "SENSOR") (pin "C15") (pinfunction "GND_C15") (pintype "power_in"))
      (node (ref "SENSOR") (pin "C16") (pinfunction "GND_C16") (pintype "power_in"))
      (node (ref "SENSOR") (pin "C28") (pinfunction "GND_C28") (pintype "power_in"))
      (node (ref "SENSOR") (pin "D2") (pinfunction "GND_D2") (pintype "power_in"))
      (node (ref "SENSOR") (pin "D25") (pinfunction "GND_D25") (pintype "power_in"))
      (node (ref "SENSOR") (pin "D27") (pinfunction "GND_D27") (pintype "power_in"))
      (node (ref "SENSOR") (pin "D29") (pinfunction "GND_D29") (pintype "power_in"))
      (node (ref "SENSOR") (pin "E15") (pinfunction "GND_E15") (pintype "power_in"))
      (node (ref "SENSOR") (pin "E16") (pinfunction "GND_E16") (pintype "power_in"))
      (node (ref "SENSOR") (pin "E25") (pinfunction "GND_E25") (pintype "power_in"))
      (node (ref "SENSOR") (pin "E27") (pinfunction "GND_E27") (pintype "power_in"))
      (node (ref "SENSOR") (pin "E3") (pinfunction "GND_E3") (pintype "power_in"))
      (node (ref "SENSOR") (pin "E4") (pinfunction "DIO2_E4") (pintype "output"))
      (node (ref "SENSOR") (pin "F27") (pinfunction "GND_F27") (pintype "power_in"))
      (node (ref "SENSOR") (pin "F4") (pinfunction "DIO1_F4") (pintype "output"))
      (node (ref "SENSOR") (pin "G3") (pinfunction "DIO4_G3") (pintype "output"))
      (node (ref "SENSOR") (pin "G5") (pinfunction "GND_G5") (pintype "power_in"))
      (node (ref "SENSOR") (pin "H1") (pinfunction "GND_H1") (pintype "power_in"))
      (node (ref "SENSOR") (pin "H21") (pinfunction "GND_H21") (pintype "power_in"))
      (node (ref "SENSOR") (pin "H25") (pinfunction "GND_H25") (pintype "power_in"))
      (node (ref "SENSOR") (pin "H27") (pinfunction "GND_H27") (pintype "power_in"))
      (node (ref "SENSOR") (pin "H4") (pinfunction "DIO3_H4") (pintype "output"))
      (node (ref "SENSOR") (pin "H6") (pinfunction "GND_H6") (pintype "power_in"))
      (node (ref "SENSOR") (pin "H9") (pinfunction "GND_H9") (pintype "power_in"))
      (node (ref "U1") (pin "6") (pinfunction "ANODE_6") (pintype "input"))
      (node (ref "U2") (pin "6") (pinfunction "ANODE_6") (pintype "input"))
      (node (ref "U3") (pin "2") (pinfunction "GND_2") (pintype "power_in"))
      (node (ref "U3") (pin "EP") (pinfunction "EP_EP") (pintype "power_in"))
      (node (ref "U4") (pin "16") (pinfunction "DIR2_16") (pintype "input"))
      (node (ref "U4") (pin "7") (pinfunction "~{OE}_7") (pintype "input"))
      (node (ref "U4") (pin "8") (pinfunction "GND_8") (pintype "passive"))
      (node (ref "U5") (pin "6") (pinfunction "DIR4_6") (pintype "input"))
      (node (ref "U5") (pin "7") (pinfunction "~{OE}_7") (pintype "input"))
      (node (ref "U5") (pin "8") (pinfunction "GND_8") (pintype "passive"))
      (node (ref "U6") (pin "16") (pinfunction "DIR2_16") (pintype "input"))
      (node (ref "U6") (pin "7") (pinfunction "~{OE}_7") (pintype "input"))
      (node (ref "U6") (pin "8") (pinfunction "GND_8") (pintype "passive"))
      (node (ref "U7") (pin "4") (pinfunction "GND_4") (pintype "power_in"))
      (node (ref "U7") (pin "5") (pinfunction "A2_5") (pintype "input"))
      (node (ref "U7") (pin "6") (pinfunction "A1_6") (pintype "input"))
      (node (ref "U7") (pin "7") (pinfunction "A0_7") (pintype "input"))
      (node (ref "UEP") (pin "1") (pinfunction "A0_1") (pintype "input"))
      (node (ref "UEP") (pin "2") (pinfunction "A1_2") (pintype "input"))
      (node (ref "UEP") (pin "3") (pinfunction "A2_3") (pintype "input"))
      (node (ref "UEP") (pin "4") (pinfunction "GND_4") (pintype "passive"))
      (node (ref "UEP") (pin "EP") (pinfunction "EP_EP") (pintype "passive"))
      (node (ref "UNE") (pin "4") (pinfunction "VSS_4") (pintype "power_in"))
      (node (ref "UNE") (pin "EP") (pinfunction "EP_EP") (pintype "passive"))
      (node (ref "UNN") (pin "4") (pinfunction "VSS_4") (pintype "power_in"))
      (node (ref "UNN") (pin "EP") (pinfunction "EP_EP") (pintype "passive"))
      (node (ref "UNW") (pin "4") (pinfunction "VSS_4") (pintype "power_in"))
      (node (ref "UNW") (pin "EP") (pinfunction "EP_EP") (pintype "passive"))
      (node (ref "USE") (pin "4") (pinfunction "VSS_4") (pintype "power_in"))
      (node (ref "USE") (pin "EP") (pinfunction "EP_EP") (pintype "passive"))
      (node (ref "USS") (pin "4") (pinfunction "VSS_4") (pintype "power_in"))
      (node (ref "USS") (pin "EP") (pinfunction "EP_EP") (pintype "passive"))
      (node (ref "USW") (pin "4") (pinfunction "VSS_4") (pintype "power_in"))
      (node (ref "USW") (pin "EP") (pinfunction "EP_EP") (pintype "passive"))
      (node (ref "X-NORTH") (pin "102") (pinfunction "102_102") (pintype "bidirectional"))
      (node (ref "X-NORTH") (pin "103") (pinfunction "103_103") (pintype "bidirectional"))
      (node (ref "X-NORTH") (pin "108") (pinfunction "108_108") (pintype "bidirectional"))
      (node (ref "X-NORTH") (pin "114") (pinfunction "114_114") (pintype "bidirectional"))
      (node (ref "X-NORTH") (pin "12") (pinfunction "12_12") (pintype "bidirectional"))
      (node (ref "X-NORTH") (pin "120") (pinfunction "120_120") (pintype "bidirectional"))
      (node (ref "X-NORTH") (pin "126") (pinfunction "126_126") (pintype "bidirectional"))
      (node (ref "X-NORTH") (pin "132") (pinfunction "132_132") (pintype "bidirectional"))
      (node (ref "X-NORTH") (pin "138") (pinfunction "138_138") (pintype "bidirectional"))
      (node (ref "X-NORTH") (pin "139") (pinfunction "139_139") (pintype "bidirectional"))
      (node (ref "X-NORTH") (pin "18") (pinfunction "18_18") (pintype "bidirectional"))
      (node (ref "X-NORTH") (pin "24") (pinfunction "24_24") (pintype "bidirectional"))
      (node (ref "X-NORTH") (pin "30") (pinfunction "30_30") (pintype "bidirectional"))
      (node (ref "X-NORTH") (pin "36") (pinfunction "36_36") (pintype "bidirectional"))
      (node (ref "X-NORTH") (pin "42") (pinfunction "42_42") (pintype "bidirectional"))
      (node (ref "X-NORTH") (pin "43") (pinfunction "43_43") (pintype "bidirectional"))
      (node (ref "X-NORTH") (pin "48") (pinfunction "48_48") (pintype "bidirectional"))
      (node (ref "X-NORTH") (pin "54") (pinfunction "54_54") (pintype "bidirectional"))
      (node (ref "X-NORTH") (pin "60") (pinfunction "60_60") (pintype "bidirectional"))
      (node (ref "X-NORTH") (pin "66") (pinfunction "66_66") (pintype "bidirectional"))
      (node (ref "X-NORTH") (pin "72") (pinfunction "72_72") (pintype "bidirectional"))
      (node (ref "X-NORTH") (pin "78") (pinfunction "78_78") (pintype "bidirectional"))
      (node (ref "X-NORTH") (pin "84") (pinfunction "84_84") (pintype "bidirectional"))
      (node (ref "X-NORTH") (pin "90") (pinfunction "90_90") (pintype "bidirectional"))
      (node (ref "X-NORTH") (pin "96") (pinfunction "96_96") (pintype "bidirectional"))
      (node (ref "X-SOUTH") (pin "102") (pinfunction "102_102") (pintype "bidirectional"))
      (node (ref "X-SOUTH") (pin "103") (pinfunction "103_103") (pintype "bidirectional"))
      (node (ref "X-SOUTH") (pin "108") (pinfunction "108_108") (pintype "bidirectional"))
      (node (ref "X-SOUTH") (pin "114") (pinfunction "114_114") (pintype "bidirectional"))
      (node (ref "X-SOUTH") (pin "12") (pinfunction "12_12") (pintype "bidirectional"))
      (node (ref "X-SOUTH") (pin "120") (pinfunction "120_120") (pintype "bidirectional"))
      (node (ref "X-SOUTH") (pin "126") (pinfunction "126_126") (pintype "bidirectional"))
      (node (ref "X-SOUTH") (pin "132") (pinfunction "132_132") (pintype "bidirectional"))
      (node (ref "X-SOUTH") (pin "138") (pinfunction "138_138") (pintype "bidirectional"))
      (node (ref "X-SOUTH") (pin "139") (pinfunction "139_139") (pintype "bidirectional"))
      (node (ref "X-SOUTH") (pin "18") (pinfunction "18_18") (pintype "bidirectional"))
      (node (ref "X-SOUTH") (pin "24") (pinfunction "24_24") (pintype "bidirectional"))
      (node (ref "X-SOUTH") (pin "30") (pinfunction "30_30") (pintype "bidirectional"))
      (node (ref "X-SOUTH") (pin "36") (pinfunction "36_36") (pintype "bidirectional"))
      (node (ref "X-SOUTH") (pin "42") (pinfunction "42_42") (pintype "bidirectional"))
      (node (ref "X-SOUTH") (pin "43") (pinfunction "43_43") (pintype "bidirectional"))
      (node (ref "X-SOUTH") (pin "48") (pinfunction "48_48") (pintype "bidirectional"))
      (node (ref "X-SOUTH") (pin "54") (pinfunction "54_54") (pintype "bidirectional"))
      (node (ref "X-SOUTH") (pin "60") (pinfunction "60_60") (pintype "bidirectional"))
      (node (ref "X-SOUTH") (pin "66") (pinfunction "66_66") (pintype "bidirectional"))
      (node (ref "X-SOUTH") (pin "72") (pinfunction "72_72") (pintype "bidirectional"))
      (node (ref "X-SOUTH") (pin "78") (pinfunction "78_78") (pintype "bidirectional"))
      (node (ref "X-SOUTH") (pin "84") (pinfunction "84_84") (pintype "bidirectional"))
      (node (ref "X-SOUTH") (pin "90") (pinfunction "90_90") (pintype "bidirectional"))
      (node (ref "X-SOUTH") (pin "96") (pinfunction "96_96") (pintype "bidirectional"))
    )
    (net (code "4") (name "N$42") (class "Default")
      (node (ref "SENSOR") (pin "A2") (pinfunction "TANA_A2") (pintype "output"))
    )
    (net (code "5") (name "N00_N") (class "Default")
      (node (ref "R25") (pin "2") (pinfunction "2_2") (pintype "passive"))
      (node (ref "SENSOR") (pin "E6") (pinfunction "LVDS_CLK_P_E6") (pintype "input"))
      (node (ref "X-NORTH") (pin "16") (pinfunction "16_16") (pintype "bidirectional"))
    )
    (net (code "6") (name "N00_P") (class "Default")
      (node (ref "R25") (pin "1") (pinfunction "1_1") (pintype "passive"))
      (node (ref "SENSOR") (pin "E5") (pinfunction "LVDS_CLK_N_E5") (pintype "input"))
      (node (ref "X-NORTH") (pin "14") (pinfunction "14_14") (pintype "bidirectional"))
    )
    (net (code "7") (name "N01_N") (class "Default")
      (node (ref "SENSOR") (pin "G7") (pinfunction "OUTCLK_P_G7") (pintype "output"))
      (node (ref "X-NORTH") (pin "17") (pinfunction "17_17") (pintype "bidirectional"))
    )
    (net (code "8") (name "N01_P") (class "Default")
      (node (ref "SENSOR") (pin "G6") (pinfunction "OUTCLK_N_G6") (pintype "output"))
      (node (ref "X-NORTH") (pin "15") (pinfunction "15_15") (pintype "bidirectional"))
    )
    (net (code "9") (name "N02_N") (class "Default")
      (node (ref "SENSOR") (pin "F7") (pinfunction "OUT33_P_F7") (pintype "output"))
      (node (ref "X-NORTH") (pin "22") (pinfunction "22_22") (pintype "bidirectional"))
    )
    (net (code "10") (name "N02_P") (class "Default")
      (node (ref "SENSOR") (pin "F6") (pinfunction "OUT33_N_F6") (pintype "output"))
      (node (ref "X-NORTH") (pin "20") (pinfunction "20_20") (pintype "bidirectional"))
    )
    (net (code "11") (name "N03_N") (class "Default")
      (node (ref "X-NORTH") (pin "23") (pinfunction "23_23") (pintype "bidirectional"))
    )
    (net (code "12") (name "N03_P") (class "Default")
      (node (ref "X-NORTH") (pin "21") (pinfunction "21_21") (pintype "bidirectional"))
    )
    (net (code "13") (name "N04_N") (class "Default")
      (node (ref "SENSOR") (pin "E8") (pinfunction "OUT35_P_E8") (pintype "output"))
      (node (ref "X-NORTH") (pin "28") (pinfunction "28_28") (pintype "bidirectional"))
    )
    (net (code "14") (name "N04_P") (class "Default")
      (node (ref "SENSOR") (pin "E7") (pinfunction "OUT35_N_E7") (pintype "output"))
      (node (ref "X-NORTH") (pin "26") (pinfunction "26_26") (pintype "bidirectional"))
    )
    (net (code "15") (name "N05_N") (class "Default")
      (node (ref "SENSOR") (pin "H8") (pinfunction "OUT34_P_H8") (pintype "output"))
      (node (ref "X-NORTH") (pin "29") (pinfunction "29_29") (pintype "bidirectional"))
    )
    (net (code "16") (name "N05_P") (class "Default")
      (node (ref "SENSOR") (pin "H7") (pinfunction "OUT34_N_H7") (pintype "output"))
      (node (ref "X-NORTH") (pin "27") (pinfunction "27_27") (pintype "bidirectional"))
    )
    (net (code "17") (name "N06_N") (class "Default")
      (node (ref "SENSOR") (pin "F9") (pinfunction "OUT37_P_F9") (pintype "output"))
      (node (ref "X-NORTH") (pin "34") (pinfunction "34_34") (pintype "bidirectional"))
    )
    (net (code "18") (name "N06_P") (class "Default")
      (node (ref "SENSOR") (pin "F8") (pinfunction "OUT37_N_F8") (pintype "output"))
      (node (ref "X-NORTH") (pin "32") (pinfunction "32_32") (pintype "bidirectional"))
    )
    (net (code "19") (name "N07_N") (class "Default")
      (node (ref "SENSOR") (pin "G9") (pinfunction "OUT36_P_G9") (pintype "output"))
      (node (ref "X-NORTH") (pin "35") (pinfunction "35_35") (pintype "bidirectional"))
    )
    (net (code "20") (name "N07_P") (class "Default")
      (node (ref "SENSOR") (pin "G8") (pinfunction "OUT36_N_G8") (pintype "output"))
      (node (ref "X-NORTH") (pin "33") (pinfunction "33_33") (pintype "bidirectional"))
    )
    (net (code "21") (name "N08_N") (class "Default")
      (node (ref "SENSOR") (pin "E10") (pinfunction "OUT38_P_E10") (pintype "output"))
      (node (ref "X-NORTH") (pin "40") (pinfunction "40_40") (pintype "bidirectional"))
    )
    (net (code "22") (name "N08_P") (class "Default")
      (node (ref "SENSOR") (pin "E9") (pinfunction "OUT38_N_E9") (pintype "output"))
      (node (ref "X-NORTH") (pin "38") (pinfunction "38_38") (pintype "bidirectional"))
    )
    (net (code "23") (name "N09_N") (class "Default")
      (node (ref "SENSOR") (pin "G11") (pinfunction "OUT39_P_G11") (pintype "output"))
      (node (ref "X-NORTH") (pin "41") (pinfunction "41_41") (pintype "bidirectional"))
    )
    (net (code "24") (name "N09_P") (class "Default")
      (node (ref "SENSOR") (pin "G10") (pinfunction "OUT39_N_G10") (pintype "output"))
      (node (ref "X-NORTH") (pin "39") (pinfunction "39_39") (pintype "bidirectional"))
    )
    (net (code "25") (name "N10_N") (class "Default")
      (node (ref "SENSOR") (pin "F11") (pinfunction "OUT40_P_F11") (pintype "output"))
      (node (ref "X-NORTH") (pin "46") (pinfunction "46_46") (pintype "bidirectional"))
    )
    (net (code "26") (name "N10_P") (class "Default")
      (node (ref "SENSOR") (pin "F10") (pinfunction "OUT40_N_F10") (pintype "output"))
      (node (ref "X-NORTH") (pin "44") (pinfunction "44_44") (pintype "bidirectional"))
    )
    (net (code "27") (name "N11_N") (class "Default")
      (node (ref "SENSOR") (pin "H12") (pinfunction "OUT41_P_H12") (pintype "output"))
      (node (ref "X-NORTH") (pin "47") (pinfunction "47_47") (pintype "bidirectional"))
    )
    (net (code "28") (name "N11_P") (class "Default")
      (node (ref "SENSOR") (pin "H11") (pinfunction "OUT41_N_H11") (pintype "output"))
      (node (ref "X-NORTH") (pin "45") (pinfunction "45_45") (pintype "bidirectional"))
    )
    (net (code "29") (name "N12_N") (class "Default")
      (node (ref "SENSOR") (pin "E12") (pinfunction "OUT42_P_E12") (pintype "output"))
      (node (ref "X-NORTH") (pin "52") (pinfunction "52_52") (pintype "bidirectional"))
    )
    (net (code "30") (name "N12_P") (class "Default")
      (node (ref "SENSOR") (pin "E11") (pinfunction "OUT42_N_E11") (pintype "output"))
      (node (ref "X-NORTH") (pin "50") (pinfunction "50_50") (pintype "bidirectional"))
    )
    (net (code "31") (name "N13_N") (class "Default")
      (node (ref "SENSOR") (pin "G13") (pinfunction "OUT43_P_G13") (pintype "output"))
      (node (ref "X-NORTH") (pin "53") (pinfunction "53_53") (pintype "bidirectional"))
    )
    (net (code "32") (name "N13_P") (class "Default")
      (node (ref "SENSOR") (pin "G12") (pinfunction "OUT43_N_G12") (pintype "output"))
      (node (ref "X-NORTH") (pin "51") (pinfunction "51_51") (pintype "bidirectional"))
    )
    (net (code "33") (name "N14_N") (class "Default")
      (node (ref "SENSOR") (pin "F13") (pinfunction "OUT44_P_F13") (pintype "output"))
      (node (ref "X-NORTH") (pin "58") (pinfunction "58_58") (pintype "bidirectional"))
    )
    (net (code "34") (name "N14_P") (class "Default")
      (node (ref "SENSOR") (pin "F12") (pinfunction "OUT44_N_F12") (pintype "output"))
      (node (ref "X-NORTH") (pin "56") (pinfunction "56_56") (pintype "bidirectional"))
    )
    (net (code "35") (name "N15_N") (class "Default")
      (node (ref "SENSOR") (pin "H14") (pinfunction "OUT45_P_H14") (pintype "output"))
      (node (ref "X-NORTH") (pin "59") (pinfunction "59_59") (pintype "bidirectional"))
    )
    (net (code "36") (name "N15_P") (class "Default")
      (node (ref "SENSOR") (pin "H13") (pinfunction "OUT45_N_H13") (pintype "output"))
      (node (ref "X-NORTH") (pin "57") (pinfunction "57_57") (pintype "bidirectional"))
    )
    (net (code "37") (name "N16_N") (class "Default")
      (node (ref "SENSOR") (pin "E14") (pinfunction "OUT46_P_E14") (pintype "output"))
      (node (ref "X-NORTH") (pin "64") (pinfunction "64_64") (pintype "bidirectional"))
    )
    (net (code "38") (name "N16_P") (class "Default")
      (node (ref "SENSOR") (pin "E13") (pinfunction "OUT46_N_E13") (pintype "output"))
      (node (ref "X-NORTH") (pin "62") (pinfunction "62_62") (pintype "bidirectional"))
    )
    (net (code "39") (name "N17_N") (class "Default")
      (node (ref "SENSOR") (pin "G15") (pinfunction "OUT47_P_G15") (pintype "output"))
      (node (ref "X-NORTH") (pin "65") (pinfunction "65_65") (pintype "bidirectional"))
    )
    (net (code "40") (name "N17_P") (class "Default")
      (node (ref "SENSOR") (pin "G14") (pinfunction "OUT47_N_G14") (pintype "output"))
      (node (ref "X-NORTH") (pin "63") (pinfunction "63_63") (pintype "bidirectional"))
    )
    (net (code "41") (name "N18_N") (class "Default")
      (node (ref "SENSOR") (pin "F15") (pinfunction "OUT48_P_F15") (pintype "output"))
      (node (ref "X-NORTH") (pin "70") (pinfunction "70_70") (pintype "bidirectional"))
    )
    (net (code "42") (name "N18_P") (class "Default")
      (node (ref "SENSOR") (pin "F14") (pinfunction "OUT48_N_F14") (pintype "output"))
      (node (ref "X-NORTH") (pin "68") (pinfunction "68_68") (pintype "bidirectional"))
    )
    (net (code "43") (name "N19_N") (class "Default")
      (node (ref "SENSOR") (pin "G17") (pinfunction "OUT50_P_G17") (pintype "output"))
      (node (ref "X-NORTH") (pin "71") (pinfunction "71_71") (pintype "bidirectional"))
    )
    (net (code "44") (name "N19_P") (class "Default")
      (node (ref "SENSOR") (pin "G16") (pinfunction "OUT50_N_G16") (pintype "output"))
      (node (ref "X-NORTH") (pin "69") (pinfunction "69_69") (pintype "bidirectional"))
    )
    (net (code "45") (name "N20_N") (class "Default")
      (node (ref "SENSOR") (pin "F17") (pinfunction "OUT49_P_F17") (pintype "output"))
      (node (ref "X-NORTH") (pin "76") (pinfunction "76_76") (pintype "bidirectional"))
    )
    (net (code "46") (name "N20_P") (class "Default")
      (node (ref "SENSOR") (pin "F16") (pinfunction "OUT49_N_F16") (pintype "output"))
      (node (ref "X-NORTH") (pin "74") (pinfunction "74_74") (pintype "bidirectional"))
    )
    (net (code "47") (name "N21_N") (class "Default")
      (node (ref "SENSOR") (pin "H18") (pinfunction "OUT52_P_H18") (pintype "output"))
      (node (ref "X-NORTH") (pin "77") (pinfunction "77_77") (pintype "bidirectional"))
    )
    (net (code "48") (name "N21_P") (class "Default")
      (node (ref "SENSOR") (pin "H17") (pinfunction "OUT52_N_H17") (pintype "output"))
      (node (ref "X-NORTH") (pin "75") (pinfunction "75_75") (pintype "bidirectional"))
    )
    (net (code "49") (name "N22_N") (class "Default")
      (node (ref "SENSOR") (pin "E18") (pinfunction "OUT51_P_E18") (pintype "output"))
      (node (ref "X-NORTH") (pin "82") (pinfunction "82_82") (pintype "bidirectional"))
    )
    (net (code "50") (name "N22_P") (class "Default")
      (node (ref "SENSOR") (pin "E17") (pinfunction "OUT51_N_E17") (pintype "output"))
      (node (ref "X-NORTH") (pin "80") (pinfunction "80_80") (pintype "bidirectional"))
    )
    (net (code "51") (name "N23_N") (class "Default")
      (node (ref "SENSOR") (pin "G19") (pinfunction "OUT54_P_G19") (pintype "output"))
      (node (ref "X-NORTH") (pin "83") (pinfunction "83_83") (pintype "bidirectional"))
    )
    (net (code "52") (name "N23_P") (class "Default")
      (node (ref "SENSOR") (pin "G18") (pinfunction "OUT54_N_G18") (pintype "output"))
      (node (ref "X-NORTH") (pin "81") (pinfunction "81_81") (pintype "bidirectional"))
    )
    (net (code "53") (name "N24_N") (class "Default")
      (node (ref "SENSOR") (pin "F19") (pinfunction "OUT53_P_F19") (pintype "output"))
      (node (ref "X-NORTH") (pin "88") (pinfunction "88_88") (pintype "bidirectional"))
    )
    (net (code "54") (name "N24_P") (class "Default")
      (node (ref "SENSOR") (pin "F18") (pinfunction "OUT53_N_F18") (pintype "output"))
      (node (ref "X-NORTH") (pin "86") (pinfunction "86_86") (pintype "bidirectional"))
    )
    (net (code "55") (name "N25_N") (class "Default")
      (node (ref "SENSOR") (pin "H20") (pinfunction "OUT56_P_H20") (pintype "output"))
      (node (ref "X-NORTH") (pin "89") (pinfunction "89_89") (pintype "bidirectional"))
    )
    (net (code "56") (name "N25_P") (class "Default")
      (node (ref "SENSOR") (pin "H19") (pinfunction "OUT56_N_H19") (pintype "output"))
      (node (ref "X-NORTH") (pin "87") (pinfunction "87_87") (pintype "bidirectional"))
    )
    (net (code "57") (name "N26_N") (class "Default")
      (node (ref "SENSOR") (pin "E20") (pinfunction "OUT55_P_E20") (pintype "output"))
      (node (ref "X-NORTH") (pin "94") (pinfunction "94_94") (pintype "bidirectional"))
    )
    (net (code "58") (name "N26_P") (class "Default")
      (node (ref "SENSOR") (pin "E19") (pinfunction "OUT55_N_E19") (pintype "output"))
      (node (ref "X-NORTH") (pin "92") (pinfunction "92_92") (pintype "bidirectional"))
    )
    (net (code "59") (name "N27_N") (class "Default")
      (node (ref "SENSOR") (pin "G21") (pinfunction "OUT58_P_G21") (pintype "output"))
      (node (ref "X-NORTH") (pin "95") (pinfunction "95_95") (pintype "bidirectional"))
    )
    (net (code "60") (name "N27_P") (class "Default")
      (node (ref "SENSOR") (pin "G20") (pinfunction "OUT58_N_G20") (pintype "output"))
      (node (ref "X-NORTH") (pin "93") (pinfunction "93_93") (pintype "bidirectional"))
    )
    (net (code "61") (name "N28_N") (class "Default")
      (node (ref "SENSOR") (pin "F21") (pinfunction "OUT57_P_F21") (pintype "output"))
      (node (ref "X-NORTH") (pin "100") (pinfunction "100_100") (pintype "bidirectional"))
    )
    (net (code "62") (name "N28_P") (class "Default")
      (node (ref "SENSOR") (pin "F20") (pinfunction "OUT57_N_F20") (pintype "output"))
      (node (ref "X-NORTH") (pin "98") (pinfunction "98_98") (pintype "bidirectional"))
    )
    (net (code "63") (name "N29_N") (class "Default")
      (node (ref "SENSOR") (pin "G23") (pinfunction "OUT61_P_G23") (pintype "output"))
      (node (ref "X-NORTH") (pin "101") (pinfunction "101_101") (pintype "bidirectional"))
    )
    (net (code "64") (name "N29_P") (class "Default")
      (node (ref "SENSOR") (pin "G22") (pinfunction "OUT61_N_G22") (pintype "output"))
      (node (ref "X-NORTH") (pin "99") (pinfunction "99_99") (pintype "bidirectional"))
    )
    (net (code "65") (name "N30_N") (class "Default")
      (node (ref "SENSOR") (pin "E22") (pinfunction "OUT59_P_E22") (pintype "output"))
      (node (ref "X-NORTH") (pin "106") (pinfunction "106_106") (pintype "bidirectional"))
    )
    (net (code "66") (name "N30_P") (class "Default")
      (node (ref "SENSOR") (pin "E21") (pinfunction "OUT59_N_E21") (pintype "output"))
      (node (ref "X-NORTH") (pin "104") (pinfunction "104_104") (pintype "bidirectional"))
    )
    (net (code "67") (name "N31_N") (class "Default")
      (node (ref "SENSOR") (pin "H24") (pinfunction "OUT63_P_H24") (pintype "output"))
      (node (ref "X-NORTH") (pin "107") (pinfunction "107_107") (pintype "bidirectional"))
    )
    (net (code "68") (name "N31_P") (class "Default")
      (node (ref "SENSOR") (pin "H23") (pinfunction "OUT63_N_H23") (pintype "output"))
      (node (ref "X-NORTH") (pin "105") (pinfunction "105_105") (pintype "bidirectional"))
    )
    (net (code "69") (name "N32_N") (class "Default")
      (node (ref "SENSOR") (pin "F23") (pinfunction "OUT60_P_F23") (pintype "output"))
      (node (ref "X-NORTH") (pin "112") (pinfunction "112_112") (pintype "bidirectional"))
    )
    (net (code "70") (name "N32_P") (class "Default")
      (node (ref "SENSOR") (pin "F22") (pinfunction "OUT60_N_F22") (pintype "output"))
      (node (ref "X-NORTH") (pin "110") (pinfunction "110_110") (pintype "bidirectional"))
    )
    (net (code "71") (name "N33_N") (class "Default")
      (node (ref "SENSOR") (pin "G25") (pinfunction "OUT64_P_G25") (pintype "output"))
      (node (ref "X-NORTH") (pin "113") (pinfunction "113_113") (pintype "bidirectional"))
    )
    (net (code "72") (name "N33_P") (class "Default")
      (node (ref "SENSOR") (pin "G24") (pinfunction "OUT64_N_G24") (pintype "output"))
      (node (ref "X-NORTH") (pin "111") (pinfunction "111_111") (pintype "bidirectional"))
    )
    (net (code "73") (name "N34_N") (class "Default")
      (node (ref "SENSOR") (pin "E24") (pinfunction "OUT62_P_E24") (pintype "output"))
      (node (ref "X-NORTH") (pin "118") (pinfunction "118_118") (pintype "bidirectional"))
    )
    (net (code "74") (name "N34_P") (class "Default")
      (node (ref "SENSOR") (pin "E23") (pinfunction "OUT62_N_E23") (pintype "output"))
      (node (ref "X-NORTH") (pin "116") (pinfunction "116_116") (pintype "bidirectional"))
    )
    (net (code "75") (name "N35_N") (class "Default")
      (node (ref "U6") (pin "4") (pinfunction "A4_4") (pintype "bidirectional"))
      (node (ref "X-NORTH") (pin "119") (pinfunction "119_119") (pintype "bidirectional"))
    )
    (net (code "76") (name "N35_P") (class "Default")
      (node (ref "U6") (pin "3") (pinfunction "A3_3") (pintype "bidirectional"))
      (node (ref "X-NORTH") (pin "117") (pinfunction "117_117") (pintype "bidirectional"))
    )
    (net (code "77") (name "N36_N") (class "Default")
      (node (ref "X-NORTH") (pin "124") (pinfunction "124_124") (pintype "bidirectional"))
    )
    (net (code "78") (name "N36_P") (class "Default")
      (node (ref "X-NORTH") (pin "122") (pinfunction "122_122") (pintype "bidirectional"))
    )
    (net (code "79") (name "N37_N") (class "Default")
      (node (ref "U5") (pin "3") (pinfunction "A3_3") (pintype "bidirectional"))
      (node (ref "X-NORTH") (pin "125") (pinfunction "125_125") (pintype "bidirectional"))
    )
    (net (code "80") (name "N37_P") (class "Default")
      (node (ref "U5") (pin "4") (pinfunction "A4_4") (pintype "bidirectional"))
      (node (ref "X-NORTH") (pin "123") (pinfunction "123_123") (pintype "bidirectional"))
    )
    (net (code "81") (name "N38_N") (class "Default")
      (node (ref "U6") (pin "2") (pinfunction "A2_2") (pintype "bidirectional"))
      (node (ref "X-NORTH") (pin "130") (pinfunction "130_130") (pintype "bidirectional"))
    )
    (net (code "82") (name "N38_P") (class "Default")
      (node (ref "U6") (pin "1") (pinfunction "A1_1") (pintype "bidirectional"))
      (node (ref "X-NORTH") (pin "128") (pinfunction "128_128") (pintype "bidirectional"))
    )
    (net (code "83") (name "N39_N") (class "Default")
      (node (ref "U5") (pin "1") (pinfunction "A1_1") (pintype "bidirectional"))
      (node (ref "X-NORTH") (pin "131") (pinfunction "131_131") (pintype "bidirectional"))
    )
    (net (code "84") (name "N39_P") (class "Default")
      (node (ref "U5") (pin "2") (pinfunction "A2_2") (pintype "bidirectional"))
      (node (ref "X-NORTH") (pin "129") (pinfunction "129_129") (pintype "bidirectional"))
    )
    (net (code "85") (name "N_CHK_EN") (class "Default")
      (node (ref "X-NORTH") (pin "8") (pinfunction "8_8") (pintype "bidirectional"))
    )
    (net (code "86") (name "N_CHK_V") (class "Default")
      (node (ref "C2") (pin "1") (pinfunction "1_1") (pintype "passive"))
      (node (ref "C3") (pin "1") (pinfunction "1_1") (pintype "passive"))
      (node (ref "C4") (pin "1") (pinfunction "1_1") (pintype "passive"))
      (node (ref "R19") (pin "1") (pinfunction "1_1") (pintype "passive"))
      (node (ref "TP1") (pin "TP") (pinfunction "TP_TP") (pintype "input"))
      (node (ref "UNE") (pin "8") (pinfunction "VDD_8") (pintype "power_in"))
      (node (ref "UNN") (pin "8") (pinfunction "VDD_8") (pintype "power_in"))
      (node (ref "UNW") (pin "8") (pinfunction "VDD_8") (pintype "power_in"))
      (node (ref "X-NORTH") (pin "10") (pinfunction "10_10") (pintype "bidirectional"))
    )
    (net (code "87") (name "N_I2C_EN") (class "Default")
      (node (ref "X-NORTH") (pin "137") (pinfunction "137_137") (pintype "bidirectional"))
    )
    (net (code "88") (name "N_I2C_V") (class "Default")
      (node (ref "C1") (pin "1") (pinfunction "1_1") (pintype "passive"))
      (node (ref "R1X") (pin "1") (pinfunction "1_1") (pintype "passive"))
      (node (ref "UEP") (pin "8") (pinfunction "VCC_8") (pintype "power_in"))
      (node (ref "X-NORTH") (pin "135") (pinfunction "135_135") (pintype "bidirectional"))
    )
    (net (code "89") (name "N_REF") (class "Default")
      (node (ref "R19") (pin "2") (pinfunction "2_2") (pintype "passive"))
      (node (ref "TP2") (pin "TP") (pinfunction "TP_TP") (pintype "input"))
      (node (ref "U1") (pin "1") (pinfunction "CATHODE_1") (pintype "output"))
      (node (ref "U1") (pin "3") (pinfunction "REF_3") (pintype "input"))
      (node (ref "UNE") (pin "2") (pinfunction "VINA-_2") (pintype "input"))
      (node (ref "UNE") (pin "5") (pinfunction "VINB+_5") (pintype "input"))
      (node (ref "UNN") (pin "2") (pinfunction "VINA-_2") (pintype "input"))
      (node (ref "UNN") (pin "5") (pinfunction "VINB+_5") (pintype "input"))
      (node (ref "UNW") (pin "2") (pinfunction "VINA-_2") (pintype "input"))
      (node (ref "UNW") (pin "5") (pinfunction "VINB+_5") (pintype "input"))
    )
    (net (code "90") (name "N_SCK") (class "Default")
      (node (ref "U4") (pin "4") (pinfunction "A4_4") (pintype "bidirectional"))
      (node (ref "X-NORTH") (pin "144") (pinfunction "144_144") (pintype "bidirectional"))
    )
    (net (code "91") (name "N_SCL") (class "Default")
      (node (ref "UEP") (pin "6") (pinfunction "SCL_6") (pintype "input"))
      (node (ref "X-NORTH") (pin "143") (pinfunction "143_143") (pintype "bidirectional"))
    )
    (net (code "92") (name "N_SDA") (class "Default")
      (node (ref "UEP") (pin "5") (pinfunction "SDA_5") (pintype "bidirectional"))
      (node (ref "X-NORTH") (pin "141") (pinfunction "141_141") (pintype "bidirectional"))
    )
    (net (code "93") (name "N_SDI") (class "Default")
      (node (ref "U4") (pin "2") (pinfunction "A2_2") (pintype "bidirectional"))
      (node (ref "X-NORTH") (pin "140") (pinfunction "140_140") (pintype "bidirectional"))
    )
    (net (code "94") (name "N_SDO") (class "Default")
      (node (ref "U4") (pin "3") (pinfunction "A3_3") (pintype "bidirectional"))
      (node (ref "X-NORTH") (pin "142") (pinfunction "142_142") (pintype "bidirectional"))
    )
    (net (code "95") (name "N_SPI_EN") (class "Default")
      (node (ref "U4") (pin "1") (pinfunction "A1_1") (pintype "bidirectional"))
      (node (ref "X-NORTH") (pin "136") (pinfunction "136_136") (pintype "bidirectional"))
    )
    (net (code "96") (name "N_SPI_V") (class "Default")
      (node (ref "C59") (pin "1") (pinfunction "1_1") (pintype "passive"))
      (node (ref "U4") (pin "14") (pinfunction "VCCA_14") (pintype "power_in"))
      (node (ref "U4") (pin "15") (pinfunction "DIR1_15") (pintype "input"))
      (node (ref "U4") (pin "5") (pinfunction "DIR3_5") (pintype "input"))
      (node (ref "U4") (pin "6") (pinfunction "DIR4_6") (pintype "input"))
      (node (ref "X-NORTH") (pin "134") (pinfunction "134_134") (pintype "bidirectional"))
    )
    (net (code "97") (name "N_VE") (class "Default")
      (node (ref "C22") (pin "1") (pinfunction "1_1") (pintype "passive"))
      (node (ref "C23") (pin "1") (pinfunction "1_1") (pintype "passive"))
      (node (ref "C24") (pin "1") (pinfunction "1_1") (pintype "passive"))
      (node (ref "C25") (pin "1") (pinfunction "1_1") (pintype "passive"))
      (node (ref "C26") (pin "1") (pinfunction "1_1") (pintype "passive"))
      (node (ref "C27") (pin "1") (pinfunction "1_1") (pintype "passive"))
      (node (ref "C28") (pin "1") (pinfunction "1_1") (pintype "passive"))
      (node (ref "C50") (pin "1") (pinfunction "1_1") (pintype "passive"))
      (node (ref "C51") (pin "1") (pinfunction "1_1") (pintype "passive"))
      (node (ref "C52") (pin "1") (pinfunction "1_1") (pintype "passive"))
      (node (ref "C53") (pin "1") (pinfunction "1_1") (pintype "passive"))
      (node (ref "C54") (pin "1") (pinfunction "1_1") (pintype "passive"))
      (node (ref "C55") (pin "1") (pinfunction "1_1") (pintype "passive"))
      (node (ref "C56") (pin "1") (pinfunction "1_1") (pintype "passive"))
      (node (ref "C67") (pin "1") (pinfunction "1_1") (pintype "passive"))
      (node (ref "C69") (pin "1") (pinfunction "1_1") (pintype "passive"))
      (node (ref "C75") (pin "1") (pinfunction "1_1") (pintype "passive"))
      (node (ref "C76") (pin "1") (pinfunction "1_1") (pintype "passive"))
      (node (ref "C77") (pin "1") (pinfunction "1_1") (pintype "passive"))
      (node (ref "C84") (pin "1") (pinfunction "1_1") (pintype "passive"))
      (node (ref "C85") (pin "1") (pinfunction "1_1") (pintype "passive"))
      (node (ref "C86") (pin "1") (pinfunction "1_1") (pintype "passive"))
      (node (ref "C93") (pin "1") (pinfunction "1_1") (pintype "passive"))
      (node (ref "SENSOR") (pin "C26") (pinfunction "VDD33_C26") (pintype "power_in"))
      (node (ref "SENSOR") (pin "C27") (pinfunction "VDD33_C27") (pintype "power_in"))
      (node (ref "SENSOR") (pin "D26") (pinfunction "VDD33_D26") (pintype "power_in"))
      (node (ref "SENSOR") (pin "D3") (pinfunction "VDD33_D3") (pintype "power_in"))
      (node (ref "SENSOR") (pin "E26") (pinfunction "VDD33_E26") (pintype "power_in"))
      (node (ref "SENSOR") (pin "F26") (pinfunction "VDD33_F26") (pintype "power_in"))
      (node (ref "SENSOR") (pin "F5") (pinfunction "VDD33_F5") (pintype "power_in"))
      (node (ref "TP7") (pin "TP") (pinfunction "TP_TP") (pintype "input"))
      (node (ref "U4") (pin "13") (pinfunction "VCCB_13") (pintype "power_in"))
      (node (ref "U5") (pin "13") (pinfunction "VCCB_13") (pintype "power_in"))
      (node (ref "U6") (pin "13") (pinfunction "VCCB_13") (pintype "power_in"))
      (node (ref "X-NORTH") (pin "109") (pinfunction "109_109") (pintype "bidirectional"))
      (node (ref "X-NORTH") (pin "115") (pinfunction "115_115") (pintype "bidirectional"))
      (node (ref "X-NORTH") (pin "121") (pinfunction "121_121") (pintype "bidirectional"))
      (node (ref "X-NORTH") (pin "127") (pinfunction "127_127") (pintype "bidirectional"))
      (node (ref "X-NORTH") (pin "133") (pinfunction "133_133") (pintype "bidirectional"))
    )
    (net (code "98") (name "N_VE_CV") (class "Default")
      (node (ref "C10") (pin "1") (pinfunction "1_1") (pintype "passive"))
      (node (ref "R7") (pin "1") (pinfunction "1_1") (pintype "passive"))
      (node (ref "X-NORTH") (pin "6") (pinfunction "6_6") (pintype "bidirectional"))
    )
    (net (code "99") (name "N_VE_OV") (class "Default")
      (node (ref "UNE") (pin "7") (pinfunction "OUTB_7") (pintype "output"))
      (node (ref "X-NORTH") (pin "5") (pinfunction "5_5") (pintype "bidirectional"))
    )
    (net (code "100") (name "N_VE_UV") (class "Default")
      (node (ref "UNE") (pin "1") (pinfunction "OUTA_1") (pintype "output"))
      (node (ref "X-NORTH") (pin "11") (pinfunction "11_11") (pintype "bidirectional"))
    )
    (net (code "101") (name "N_VN") (class "Default")
      (node (ref "C31") (pin "1") (pinfunction "1_1") (pintype "passive"))
      (node (ref "C32") (pin "1") (pinfunction "1_1") (pintype "passive"))
      (node (ref "C33") (pin "1") (pinfunction "1_1") (pintype "passive"))
      (node (ref "C34") (pin "1") (pinfunction "1_1") (pintype "passive"))
      (node (ref "C35") (pin "1") (pinfunction "1_1") (pintype "passive"))
      (node (ref "C36") (pin "1") (pinfunction "1_1") (pintype "passive"))
      (node (ref "C37") (pin "1") (pinfunction "1_1") (pintype "passive"))
      (node (ref "C38") (pin "1") (pinfunction "1_1") (pintype "passive"))
      (node (ref "C39") (pin "1") (pinfunction "1_1") (pintype "passive"))
      (node (ref "C40") (pin "1") (pinfunction "1_1") (pintype "passive"))
      (node (ref "C41") (pin "1") (pinfunction "1_1") (pintype "passive"))
      (node (ref "C42") (pin "1") (pinfunction "1_1") (pintype "passive"))
      (node (ref "C43") (pin "1") (pinfunction "1_1") (pintype "passive"))
      (node (ref "C44") (pin "1") (pinfunction "1_1") (pintype "passive"))
      (node (ref "C68") (pin "1") (pinfunction "1_1") (pintype "passive"))
      (node (ref "C70") (pin "1") (pinfunction "1_1") (pintype "passive"))
      (node (ref "C78") (pin "1") (pinfunction "1_1") (pintype "passive"))
      (node (ref "C79") (pin "1") (pinfunction "1_1") (pintype "passive"))
      (node (ref "C80") (pin "1") (pinfunction "1_1") (pintype "passive"))
      (node (ref "C87") (pin "1") (pinfunction "1_1") (pintype "passive"))
      (node (ref "C88") (pin "1") (pinfunction "1_1") (pintype "passive"))
      (node (ref "C89") (pin "1") (pinfunction "1_1") (pintype "passive"))
      (node (ref "SENSOR") (pin "A10") (pinfunction "VDD18_A10") (pintype "power_in"))
      (node (ref "SENSOR") (pin "A15") (pinfunction "VDD18_A15") (pintype "power_in"))
      (node (ref "SENSOR") (pin "A16") (pinfunction "VDD18_A16") (pintype "power_in"))
      (node (ref "SENSOR") (pin "A22") (pinfunction "VDD18_A22") (pintype "power_in"))
      (node (ref "SENSOR") (pin "A26") (pinfunction "VDD18_A26") (pintype "power_in"))
      (node (ref "SENSOR") (pin "A27") (pinfunction "VDD18_A27") (pintype "power_in"))
      (node (ref "SENSOR") (pin "B4") (pinfunction "VDD18_B4") (pintype "power_in"))
      (node (ref "SENSOR") (pin "E1") (pinfunction "VDD18_PLL_E1") (pintype "power_in"))
      (node (ref "SENSOR") (pin "H10") (pinfunction "VDD18_H10") (pintype "power_in"))
      (node (ref "SENSOR") (pin "H15") (pinfunction "VDD18_H15") (pintype "power_in"))
      (node (ref "SENSOR") (pin "H16") (pinfunction "VDD18_H16") (pintype "power_in"))
      (node (ref "SENSOR") (pin "H22") (pinfunction "VDD18_H22") (pintype "power_in"))
      (node (ref "SENSOR") (pin "H26") (pinfunction "VDD18_H26") (pintype "power_in"))
      (node (ref "SENSOR") (pin "H5") (pinfunction "VDD18_H5") (pintype "power_in"))
      (node (ref "TP5") (pin "TP") (pinfunction "TP_TP") (pintype "input"))
      (node (ref "U5") (pin "14") (pinfunction "VCCA_14") (pintype "power_in"))
      (node (ref "U5") (pin "15") (pinfunction "DIR1_15") (pintype "input"))
      (node (ref "U5") (pin "16") (pinfunction "DIR2_16") (pintype "input"))
      (node (ref "U5") (pin "5") (pinfunction "DIR3_5") (pintype "input"))
      (node (ref "U6") (pin "14") (pinfunction "VCCA_14") (pintype "power_in"))
      (node (ref "U6") (pin "15") (pinfunction "DIR1_15") (pintype "input"))
      (node (ref "U6") (pin "5") (pinfunction "DIR3_5") (pintype "input"))
      (node (ref "U6") (pin "6") (pinfunction "DIR4_6") (pintype "input"))
      (node (ref "X-NORTH") (pin "49") (pinfunction "49_49") (pintype "bidirectional"))
      (node (ref "X-NORTH") (pin "55") (pinfunction "55_55") (pintype "bidirectional"))
      (node (ref "X-NORTH") (pin "61") (pinfunction "61_61") (pintype "bidirectional"))
      (node (ref "X-NORTH") (pin "67") (pinfunction "67_67") (pintype "bidirectional"))
      (node (ref "X-NORTH") (pin "73") (pinfunction "73_73") (pintype "bidirectional"))
      (node (ref "X-NORTH") (pin "79") (pinfunction "79_79") (pintype "bidirectional"))
      (node (ref "X-NORTH") (pin "85") (pinfunction "85_85") (pintype "bidirectional"))
      (node (ref "X-NORTH") (pin "91") (pinfunction "91_91") (pintype "bidirectional"))
      (node (ref "X-NORTH") (pin "97") (pinfunction "97_97") (pintype "bidirectional"))
    )
    (net (code "102") (name "N_VN_CV") (class "Default")
      (node (ref "C9") (pin "1") (pinfunction "1_1") (pintype "passive"))
      (node (ref "R4") (pin "1") (pinfunction "1_1") (pintype "passive"))
      (node (ref "X-NORTH") (pin "4") (pinfunction "4_4") (pintype "bidirectional"))
    )
    (net (code "103") (name "N_VN_OV") (class "Default")
      (node (ref "UNN") (pin "7") (pinfunction "OUTB_7") (pintype "output"))
      (node (ref "X-NORTH") (pin "3") (pinfunction "3_3") (pintype "bidirectional"))
    )
    (net (code "104") (name "N_VN_UV") (class "Default")
      (node (ref "UNN") (pin "1") (pinfunction "OUTA_1") (pintype "output"))
      (node (ref "X-NORTH") (pin "9") (pinfunction "9_9") (pintype "bidirectional"))
    )
    (net (code "105") (name "N_VW") (class "Default")
      (node (ref "C57") (pin "1") (pinfunction "1_1") (pintype "passive"))
      (node (ref "C58") (pin "1") (pinfunction "1_1") (pintype "passive"))
      (node (ref "C92") (pin "1") (pinfunction "1_1") (pintype "passive"))
      (node (ref "SENSOR") (pin "E2") (pinfunction "VDD_RES_E2") (pintype "power_in"))
      (node (ref "SENSOR") (pin "G4") (pinfunction "VDD_RES_G4") (pintype "power_in"))
      (node (ref "TP8") (pin "TP") (pinfunction "TP_TP") (pintype "input"))
      (node (ref "X-NORTH") (pin "13") (pinfunction "13_13") (pintype "bidirectional"))
      (node (ref "X-NORTH") (pin "19") (pinfunction "19_19") (pintype "bidirectional"))
      (node (ref "X-NORTH") (pin "25") (pinfunction "25_25") (pintype "bidirectional"))
      (node (ref "X-NORTH") (pin "31") (pinfunction "31_31") (pintype "bidirectional"))
      (node (ref "X-NORTH") (pin "37") (pinfunction "37_37") (pintype "bidirectional"))
    )
    (net (code "106") (name "N_VW_CV") (class "Default")
      (node (ref "C8") (pin "1") (pinfunction "1_1") (pintype "passive"))
      (node (ref "R1") (pin "1") (pinfunction "1_1") (pintype "passive"))
      (node (ref "X-NORTH") (pin "2") (pinfunction "2_2") (pintype "bidirectional"))
    )
    (net (code "107") (name "N_VW_OV") (class "Default")
      (node (ref "UNW") (pin "7") (pinfunction "OUTB_7") (pintype "output"))
      (node (ref "X-NORTH") (pin "1") (pinfunction "1_1") (pintype "bidirectional"))
    )
    (net (code "108") (name "N_VW_UV") (class "Default")
      (node (ref "UNW") (pin "1") (pinfunction "OUTA_1") (pintype "output"))
      (node (ref "X-NORTH") (pin "7") (pinfunction "7_7") (pintype "bidirectional"))
    )
    (net (code "109") (name "Net-(SENSORB-CMDN)") (class "Default")
      (node (ref "C61") (pin "1") (pinfunction "1_1") (pintype "passive"))
      (node (ref "SENSOR") (pin "F1") (pinfunction "CMDN_F1") (pintype "bidirectional"))
    )
    (net (code "110") (name "Net-(SENSORB-CMDP)") (class "Default")
      (node (ref "C22") (pin "2") (pinfunction "2_2") (pintype "passive"))
      (node (ref "SENSOR") (pin "F2") (pinfunction "CMDP_F2") (pintype "bidirectional"))
    )
    (net (code "111") (name "Net-(SENSORB-CMDP_COMP)") (class "Default")
      (node (ref "C28") (pin "2") (pinfunction "2_2") (pintype "passive"))
      (node (ref "SENSOR") (pin "H3") (pinfunction "CMDP_COMP_H3") (pintype "bidirectional"))
    )
    (net (code "112") (name "Net-(SENSORB-CMDP_COMP_INV)") (class "Default")
      (node (ref "C27") (pin "2") (pinfunction "2_2") (pintype "passive"))
      (node (ref "SENSOR") (pin "F3") (pinfunction "CMDP_COMP_INV_F3") (pintype "bidirectional"))
    )
    (net (code "113") (name "Net-(SENSORB-CMD_COLAMP)") (class "Default")
      (node (ref "C25") (pin "2") (pinfunction "2_2") (pintype "passive"))
      (node (ref "SENSOR") (pin "C6") (pinfunction "CMD_COLAMP_C6") (pintype "bidirectional"))
    )
    (net (code "114") (name "Net-(SENSORB-CMD_COL_LOAD)") (class "Default")
      (node (ref "C23") (pin "2") (pinfunction "2_2") (pintype "passive"))
      (node (ref "SENSOR") (pin "B1") (pinfunction "CMD_COL_LOAD_B1") (pintype "bidirectional"))
    )
    (net (code "115") (name "Net-(SENSORB-CMD_COL_PC)") (class "Default")
      (node (ref "C26") (pin "2") (pinfunction "2_2") (pintype "passive"))
      (node (ref "SENSOR") (pin "D1") (pinfunction "CMD_COL_PC_D1") (pintype "bidirectional"))
    )
    (net (code "116") (name "Net-(SENSORB-CMD_LVDS)") (class "Default")
      (node (ref "C62") (pin "1") (pinfunction "1_1") (pintype "passive"))
      (node (ref "SENSOR") (pin "C1") (pinfunction "CMD_LVDS_C1") (pintype "bidirectional"))
    )
    (net (code "117") (name "Net-(SENSORB-CMD_RAMP)") (class "Default")
      (node (ref "C24") (pin "2") (pinfunction "2_2") (pintype "passive"))
      (node (ref "SENSOR") (pin "B29") (pinfunction "CMD_RAMP_B29") (pintype "bidirectional"))
    )
    (net (code "118") (name "Net-(SENSORB-VBGAP)") (class "Default")
      (node (ref "C64") (pin "1") (pinfunction "1_1") (pintype "passive"))
      (node (ref "SENSOR") (pin "C29") (pinfunction "VBGAP_C29") (pintype "bidirectional"))
    )
    (net (code "119") (name "Net-(SENSORB-VCLAMP)") (class "Default")
      (node (ref "C63") (pin "1") (pinfunction "1_1") (pintype "passive"))
      (node (ref "SENSOR") (pin "D4") (pinfunction "VCLAMP_D4") (pintype "bidirectional"))
    )
    (net (code "120") (name "Net-(SENSORB-VCLAMP_ADC)") (class "Default")
      (node (ref "C60") (pin "1") (pinfunction "1_1") (pintype "passive"))
      (node (ref "SENSOR") (pin "G2") (pinfunction "VCLAMP_ADC_G2") (pintype "bidirectional"))
    )
    (net (code "121") (name "Net-(SENSORB-VPCH_H)") (class "Default")
      (node (ref "C71") (pin "1") (pinfunction "1_1") (pintype "passive"))
      (node (ref "SENSOR") (pin "C4") (pinfunction "VPCH_H_C4") (pintype "bidirectional"))
    )
    (net (code "122") (name "Net-(SENSORB-VPCH_L)") (class "Default")
      (node (ref "C14") (pin "1") (pinfunction "1_1") (pintype "passive"))
      (node (ref "SENSOR") (pin "A4") (pinfunction "VPCH_L_A4") (pintype "bidirectional"))
    )
    (net (code "123") (name "Net-(SENSORB-VREF)") (class "Default")
      (node (ref "C29") (pin "1") (pinfunction "1_1") (pintype "passive"))
      (node (ref "SENSOR") (pin "A3") (pinfunction "VREF_A3") (pintype "bidirectional"))
    )
    (net (code "124") (name "Net-(SENSORB-VREF_ADC)") (class "Default")
      (node (ref "C30") (pin "1") (pinfunction "1_1") (pintype "passive"))
      (node (ref "SENSOR") (pin "B3") (pinfunction "VREF_ADC_B3") (pintype "bidirectional"))
    )
    (net (code "125") (name "Net-(SENSORB-VRES_L)") (class "Default")
      (node (ref "C15") (pin "1") (pinfunction "1_1") (pintype "passive"))
      (node (ref "SENSOR") (pin "D5") (pinfunction "VRES_L_D5") (pintype "bidirectional"))
    )
    (net (code "126") (name "Net-(SENSORB-VTF_LOW0)") (class "Default")
      (node (ref "C18") (pin "1") (pinfunction "1_1") (pintype "passive"))
      (node (ref "SENSOR") (pin "C5") (pinfunction "VTF_LOW0_C5") (pintype "bidirectional"))
    )
    (net (code "127") (name "Net-(SENSORB-VTF_LOW1)") (class "Default")
      (node (ref "C19") (pin "1") (pinfunction "1_1") (pintype "passive"))
      (node (ref "SENSOR") (pin "D6") (pinfunction "VTF_LOW1_D6") (pintype "bidirectional"))
    )
    (net (code "128") (name "Net-(SENSORB-VTF_LOW2)") (class "Default")
      (node (ref "C20") (pin "1") (pinfunction "1_1") (pintype "passive"))
      (node (ref "SENSOR") (pin "B30") (pinfunction "VTF_LOW2_B30") (pintype "bidirectional"))
    )
    (net (code "129") (name "Net-(SENSORB-VTF_LOW3)") (class "Default")
      (node (ref "C21") (pin "1") (pinfunction "1_1") (pintype "passive"))
      (node (ref "SENSOR") (pin "C30") (pinfunction "VTF_LOW3_C30") (pintype "bidirectional"))
    )
    (net (code "130") (name "Net-(U3-ADJ)") (class "Default")
      (node (ref "R21") (pin "1") (pinfunction "1_1") (pintype "passive"))
      (node (ref "R22") (pin "2") (pinfunction "2_2") (pintype "passive"))
      (node (ref "U3") (pin "5") (pinfunction "ADJ_5") (pintype "input"))
    )
    (net (code "131") (name "Net-(U6-B4)") (class "Default")
      (node (ref "TP9") (pin "TP") (pinfunction "TP_TP") (pintype "input"))
      (node (ref "U6") (pin "9") (pinfunction "B4_9") (pintype "bidirectional"))
    )
    (net (code "132") (name "Net-(UEP-WP)") (class "Default")
      (node (ref "R1X") (pin "2") (pinfunction "2_2") (pintype "passive"))
      (node (ref "R2X") (pin "1") (pinfunction "1_1") (pintype "passive"))
      (node (ref "UEP") (pin "7") (pinfunction "WP_7") (pintype "input"))
    )
    (net (code "133") (name "Net-(UNE-VINA+)") (class "Default")
      (node (ref "R7") (pin "2") (pinfunction "2_2") (pintype "passive"))
      (node (ref "R8") (pin "1") (pinfunction "1_1") (pintype "passive"))
      (node (ref "UNE") (pin "3") (pinfunction "VINA+_3") (pintype "input"))
    )
    (net (code "134") (name "Net-(UNE-VINB-)") (class "Default")
      (node (ref "R8") (pin "2") (pinfunction "2_2") (pintype "passive"))
      (node (ref "R9") (pin "1") (pinfunction "1_1") (pintype "passive"))
      (node (ref "UNE") (pin "6") (pinfunction "VINB-_6") (pintype "input"))
    )
    (net (code "135") (name "Net-(UNN-VINA+)") (class "Default")
      (node (ref "R4") (pin "2") (pinfunction "2_2") (pintype "passive"))
      (node (ref "R5") (pin "1") (pinfunction "1_1") (pintype "passive"))
      (node (ref "UNN") (pin "3") (pinfunction "VINA+_3") (pintype "input"))
    )
    (net (code "136") (name "Net-(UNN-VINB-)") (class "Default")
      (node (ref "R5") (pin "2") (pinfunction "2_2") (pintype "passive"))
      (node (ref "R6") (pin "1") (pinfunction "1_1") (pintype "passive"))
      (node (ref "UNN") (pin "6") (pinfunction "VINB-_6") (pintype "input"))
    )
    (net (code "137") (name "Net-(UNW-VINA+)") (class "Default")
      (node (ref "R1") (pin "2") (pinfunction "2_2") (pintype "passive"))
      (node (ref "R2") (pin "1") (pinfunction "1_1") (pintype "passive"))
      (node (ref "UNW") (pin "3") (pinfunction "VINA+_3") (pintype "input"))
    )
    (net (code "138") (name "Net-(UNW-VINB-)") (class "Default")
      (node (ref "R2") (pin "2") (pinfunction "2_2") (pintype "passive"))
      (node (ref "R3") (pin "1") (pinfunction "1_1") (pintype "passive"))
      (node (ref "UNW") (pin "6") (pinfunction "VINB-_6") (pintype "input"))
    )
    (net (code "139") (name "Net-(USE-VINA+)") (class "Default")
      (node (ref "R10") (pin "2") (pinfunction "2_2") (pintype "passive"))
      (node (ref "R11") (pin "1") (pinfunction "1_1") (pintype "passive"))
      (node (ref "USE") (pin "3") (pinfunction "VINA+_3") (pintype "input"))
    )
    (net (code "140") (name "Net-(USE-VINB-)") (class "Default")
      (node (ref "R11") (pin "2") (pinfunction "2_2") (pintype "passive"))
      (node (ref "R12") (pin "1") (pinfunction "1_1") (pintype "passive"))
      (node (ref "USE") (pin "6") (pinfunction "VINB-_6") (pintype "input"))
    )
    (net (code "141") (name "Net-(USS-VINA+)") (class "Default")
      (node (ref "R13") (pin "2") (pinfunction "2_2") (pintype "passive"))
      (node (ref "R14") (pin "1") (pinfunction "1_1") (pintype "passive"))
      (node (ref "USS") (pin "3") (pinfunction "VINA+_3") (pintype "input"))
    )
    (net (code "142") (name "Net-(USS-VINB-)") (class "Default")
      (node (ref "R14") (pin "2") (pinfunction "2_2") (pintype "passive"))
      (node (ref "R15") (pin "1") (pinfunction "1_1") (pintype "passive"))
      (node (ref "USS") (pin "6") (pinfunction "VINB-_6") (pintype "input"))
    )
    (net (code "143") (name "Net-(USW-VINA+)") (class "Default")
      (node (ref "R16") (pin "2") (pinfunction "2_2") (pintype "passive"))
      (node (ref "R17") (pin "1") (pinfunction "1_1") (pintype "passive"))
      (node (ref "USW") (pin "3") (pinfunction "VINA+_3") (pintype "input"))
    )
    (net (code "144") (name "Net-(USW-VINB-)") (class "Default")
      (node (ref "R17") (pin "2") (pinfunction "2_2") (pintype "passive"))
      (node (ref "R18") (pin "1") (pinfunction "1_1") (pintype "passive"))
      (node (ref "USW") (pin "6") (pinfunction "VINB-_6") (pintype "input"))
    )
    (net (code "145") (name "S00_N") (class "Default")
      (node (ref "X-SOUTH") (pin "16") (pinfunction "16_16") (pintype "bidirectional"))
    )
    (net (code "146") (name "S00_P") (class "Default")
      (node (ref "X-SOUTH") (pin "14") (pinfunction "14_14") (pintype "bidirectional"))
    )
    (net (code "147") (name "S01_N") (class "Default")
      (node (ref "X-SOUTH") (pin "17") (pinfunction "17_17") (pintype "bidirectional"))
    )
    (net (code "148") (name "S01_P") (class "Default")
      (node (ref "X-SOUTH") (pin "15") (pinfunction "15_15") (pintype "bidirectional"))
    )
    (net (code "149") (name "S02_N") (class "Default")
      (node (ref "X-SOUTH") (pin "22") (pinfunction "22_22") (pintype "bidirectional"))
    )
    (net (code "150") (name "S02_P") (class "Default")
      (node (ref "X-SOUTH") (pin "20") (pinfunction "20_20") (pintype "bidirectional"))
    )
    (net (code "151") (name "S03_N") (class "Default")
      (node (ref "X-SOUTH") (pin "23") (pinfunction "23_23") (pintype "bidirectional"))
    )
    (net (code "152") (name "S03_P") (class "Default")
      (node (ref "X-SOUTH") (pin "21") (pinfunction "21_21") (pintype "bidirectional"))
    )
    (net (code "153") (name "S04_N") (class "Default")
      (node (ref "SENSOR") (pin "C24") (pinfunction "OUT32_N_C24") (pintype "output"))
      (node (ref "X-SOUTH") (pin "28") (pinfunction "28_28") (pintype "bidirectional"))
    )
    (net (code "154") (name "S04_P") (class "Default")
      (node (ref "SENSOR") (pin "C25") (pinfunction "OUT32_P_C25") (pintype "output"))
      (node (ref "X-SOUTH") (pin "26") (pinfunction "26_26") (pintype "bidirectional"))
    )
    (net (code "155") (name "S05_N") (class "Default")
      (node (ref "X-SOUTH") (pin "29") (pinfunction "29_29") (pintype "bidirectional"))
    )
    (net (code "156") (name "S05_P") (class "Default")
      (node (ref "X-SOUTH") (pin "27") (pinfunction "27_27") (pintype "bidirectional"))
    )
    (net (code "157") (name "S06_N") (class "Default")
      (node (ref "SENSOR") (pin "D23") (pinfunction "OUT30_N_D23") (pintype "output"))
      (node (ref "X-SOUTH") (pin "34") (pinfunction "34_34") (pintype "bidirectional"))
    )
    (net (code "158") (name "S06_P") (class "Default")
      (node (ref "SENSOR") (pin "D24") (pinfunction "OUT30_P_D24") (pintype "output"))
      (node (ref "X-SOUTH") (pin "32") (pinfunction "32_32") (pintype "bidirectional"))
    )
    (net (code "159") (name "S07_N") (class "Default")
      (node (ref "SENSOR") (pin "B24") (pinfunction "OUT31_N_B24") (pintype "output"))
      (node (ref "X-SOUTH") (pin "35") (pinfunction "35_35") (pintype "bidirectional"))
    )
    (net (code "160") (name "S07_P") (class "Default")
      (node (ref "SENSOR") (pin "B25") (pinfunction "OUT31_P_B25") (pintype "output"))
      (node (ref "X-SOUTH") (pin "33") (pinfunction "33_33") (pintype "bidirectional"))
    )
    (net (code "161") (name "S08_N") (class "Default")
      (node (ref "SENSOR") (pin "D21") (pinfunction "OUT27_N_D21") (pintype "output"))
      (node (ref "X-SOUTH") (pin "40") (pinfunction "40_40") (pintype "bidirectional"))
    )
    (net (code "162") (name "S08_P") (class "Default")
      (node (ref "SENSOR") (pin "D22") (pinfunction "OUT27_P_D22") (pintype "output"))
      (node (ref "X-SOUTH") (pin "38") (pinfunction "38_38") (pintype "bidirectional"))
    )
    (net (code "163") (name "S09_N") (class "Default")
      (node (ref "SENSOR") (pin "A23") (pinfunction "OUT29_N_A23") (pintype "output"))
      (node (ref "X-SOUTH") (pin "41") (pinfunction "41_41") (pintype "bidirectional"))
    )
    (net (code "164") (name "S09_P") (class "Default")
      (node (ref "SENSOR") (pin "A24") (pinfunction "OUT29_P_A24") (pintype "output"))
      (node (ref "X-SOUTH") (pin "39") (pinfunction "39_39") (pintype "bidirectional"))
    )
    (net (code "165") (name "S10_N") (class "Default")
      (node (ref "SENSOR") (pin "C21") (pinfunction "OUT28_N_C21") (pintype "output"))
      (node (ref "X-SOUTH") (pin "46") (pinfunction "46_46") (pintype "bidirectional"))
    )
    (net (code "166") (name "S10_P") (class "Default")
      (node (ref "SENSOR") (pin "C22") (pinfunction "OUT28_P_C22") (pintype "output"))
      (node (ref "X-SOUTH") (pin "44") (pinfunction "44_44") (pintype "bidirectional"))
    )
    (net (code "167") (name "S11_N") (class "Default")
      (node (ref "SENSOR") (pin "B20") (pinfunction "OUT26_N_B20") (pintype "output"))
      (node (ref "X-SOUTH") (pin "47") (pinfunction "47_47") (pintype "bidirectional"))
    )
    (net (code "168") (name "S11_P") (class "Default")
      (node (ref "SENSOR") (pin "B21") (pinfunction "OUT26_P_B21") (pintype "output"))
      (node (ref "X-SOUTH") (pin "45") (pinfunction "45_45") (pintype "bidirectional"))
    )
    (net (code "169") (name "S12_N") (class "Default")
      (node (ref "SENSOR") (pin "D19") (pinfunction "OUT24_N_D19") (pintype "output"))
      (node (ref "X-SOUTH") (pin "52") (pinfunction "52_52") (pintype "bidirectional"))
    )
    (net (code "170") (name "S12_P") (class "Default")
      (node (ref "SENSOR") (pin "D20") (pinfunction "OUT24_P_D20") (pintype "output"))
      (node (ref "X-SOUTH") (pin "50") (pinfunction "50_50") (pintype "bidirectional"))
    )
    (net (code "171") (name "S13_N") (class "Default")
      (node (ref "SENSOR") (pin "A19") (pinfunction "OUT23_N_A19") (pintype "output"))
      (node (ref "X-SOUTH") (pin "53") (pinfunction "53_53") (pintype "bidirectional"))
    )
    (net (code "172") (name "S13_P") (class "Default")
      (node (ref "SENSOR") (pin "A20") (pinfunction "OUT23_P_A20") (pintype "output"))
      (node (ref "X-SOUTH") (pin "51") (pinfunction "51_51") (pintype "bidirectional"))
    )
    (net (code "173") (name "S14_N") (class "Default")
      (node (ref "SENSOR") (pin "C19") (pinfunction "OUT25_N_C19") (pintype "output"))
      (node (ref "X-SOUTH") (pin "58") (pinfunction "58_58") (pintype "bidirectional"))
    )
    (net (code "174") (name "S14_P") (class "Default")
      (node (ref "SENSOR") (pin "C20") (pinfunction "OUT25_P_C20") (pintype "output"))
      (node (ref "X-SOUTH") (pin "56") (pinfunction "56_56") (pintype "bidirectional"))
    )
    (net (code "175") (name "S15_N") (class "Default")
      (node (ref "SENSOR") (pin "B18") (pinfunction "OUT22_N_B18") (pintype "output"))
      (node (ref "X-SOUTH") (pin "59") (pinfunction "59_59") (pintype "bidirectional"))
    )
    (net (code "176") (name "S15_P") (class "Default")
      (node (ref "SENSOR") (pin "B19") (pinfunction "OUT22_P_B19") (pintype "output"))
      (node (ref "X-SOUTH") (pin "57") (pinfunction "57_57") (pintype "bidirectional"))
    )
    (net (code "177") (name "S16_N") (class "Default")
      (node (ref "SENSOR") (pin "C17") (pinfunction "OUT21_N_C17") (pintype "output"))
      (node (ref "X-SOUTH") (pin "64") (pinfunction "64_64") (pintype "bidirectional"))
    )
    (net (code "178") (name "S16_P") (class "Default")
      (node (ref "SENSOR") (pin "C18") (pinfunction "OUT21_P_C18") (pintype "output"))
      (node (ref "X-SOUTH") (pin "62") (pinfunction "62_62") (pintype "bidirectional"))
    )
    (net (code "179") (name "S17_N") (class "Default")
      (node (ref "SENSOR") (pin "A17") (pinfunction "OUT19_N_A17") (pintype "output"))
      (node (ref "X-SOUTH") (pin "65") (pinfunction "65_65") (pintype "bidirectional"))
    )
    (net (code "180") (name "S17_P") (class "Default")
      (node (ref "SENSOR") (pin "A18") (pinfunction "OUT19_P_A18") (pintype "output"))
      (node (ref "X-SOUTH") (pin "63") (pinfunction "63_63") (pintype "bidirectional"))
    )
    (net (code "181") (name "S18_N") (class "Default")
      (node (ref "SENSOR") (pin "D17") (pinfunction "OUT20_N_D17") (pintype "output"))
      (node (ref "X-SOUTH") (pin "70") (pinfunction "70_70") (pintype "bidirectional"))
    )
    (net (code "182") (name "S18_P") (class "Default")
      (node (ref "SENSOR") (pin "D18") (pinfunction "OUT20_P_D18") (pintype "output"))
      (node (ref "X-SOUTH") (pin "68") (pinfunction "68_68") (pintype "bidirectional"))
    )
    (net (code "183") (name "S19_N") (class "Default")
      (node (ref "SENSOR") (pin "B16") (pinfunction "OUT18_N_B16") (pintype "output"))
      (node (ref "X-SOUTH") (pin "71") (pinfunction "71_71") (pintype "bidirectional"))
    )
    (net (code "184") (name "S19_P") (class "Default")
      (node (ref "SENSOR") (pin "B17") (pinfunction "OUT18_P_B17") (pintype "output"))
      (node (ref "X-SOUTH") (pin "69") (pinfunction "69_69") (pintype "bidirectional"))
    )
    (net (code "185") (name "S20_N") (class "Default")
      (node (ref "SENSOR") (pin "D15") (pinfunction "OUT17_N_D15") (pintype "output"))
      (node (ref "X-SOUTH") (pin "76") (pinfunction "76_76") (pintype "bidirectional"))
    )
    (net (code "186") (name "S20_P") (class "Default")
      (node (ref "SENSOR") (pin "D16") (pinfunction "OUT17_P_D16") (pintype "output"))
      (node (ref "X-SOUTH") (pin "74") (pinfunction "74_74") (pintype "bidirectional"))
    )
    (net (code "187") (name "S21_N") (class "Default")
      (node (ref "SENSOR") (pin "B14") (pinfunction "OUT16_N_B14") (pintype "output"))
      (node (ref "X-SOUTH") (pin "77") (pinfunction "77_77") (pintype "bidirectional"))
    )
    (net (code "188") (name "S21_P") (class "Default")
      (node (ref "SENSOR") (pin "B15") (pinfunction "OUT16_P_B15") (pintype "output"))
      (node (ref "X-SOUTH") (pin "75") (pinfunction "75_75") (pintype "bidirectional"))
    )
    (net (code "189") (name "S22_N") (class "Default")
      (node (ref "SENSOR") (pin "D13") (pinfunction "OUT15_N_D13") (pintype "output"))
      (node (ref "X-SOUTH") (pin "82") (pinfunction "82_82") (pintype "bidirectional"))
    )
    (net (code "190") (name "S22_P") (class "Default")
      (node (ref "SENSOR") (pin "D14") (pinfunction "OUT15_P_D14") (pintype "output"))
      (node (ref "X-SOUTH") (pin "80") (pinfunction "80_80") (pintype "bidirectional"))
    )
    (net (code "191") (name "S23_N") (class "Default")
      (node (ref "SENSOR") (pin "A13") (pinfunction "OUT13_N_A13") (pintype "output"))
      (node (ref "X-SOUTH") (pin "83") (pinfunction "83_83") (pintype "bidirectional"))
    )
    (net (code "192") (name "S23_P") (class "Default")
      (node (ref "SENSOR") (pin "A14") (pinfunction "OUT13_P_A14") (pintype "output"))
      (node (ref "X-SOUTH") (pin "81") (pinfunction "81_81") (pintype "bidirectional"))
    )
    (net (code "193") (name "S24_N") (class "Default")
      (node (ref "SENSOR") (pin "C13") (pinfunction "OUT14_N_C13") (pintype "output"))
      (node (ref "X-SOUTH") (pin "88") (pinfunction "88_88") (pintype "bidirectional"))
    )
    (net (code "194") (name "S24_P") (class "Default")
      (node (ref "SENSOR") (pin "C14") (pinfunction "OUT14_P_C14") (pintype "output"))
      (node (ref "X-SOUTH") (pin "86") (pinfunction "86_86") (pintype "bidirectional"))
    )
    (net (code "195") (name "S25_N") (class "Default")
      (node (ref "SENSOR") (pin "B12") (pinfunction "OUT12_N_B12") (pintype "output"))
      (node (ref "X-SOUTH") (pin "89") (pinfunction "89_89") (pintype "bidirectional"))
    )
    (net (code "196") (name "S25_P") (class "Default")
      (node (ref "SENSOR") (pin "B13") (pinfunction "OUT12_P_B13") (pintype "output"))
      (node (ref "X-SOUTH") (pin "87") (pinfunction "87_87") (pintype "bidirectional"))
    )
    (net (code "197") (name "S26_N") (class "Default")
      (node (ref "SENSOR") (pin "D11") (pinfunction "OUT10_N_D11") (pintype "output"))
      (node (ref "X-SOUTH") (pin "94") (pinfunction "94_94") (pintype "bidirectional"))
    )
    (net (code "198") (name "S26_P") (class "Default")
      (node (ref "SENSOR") (pin "D12") (pinfunction "OUT10_P_D12") (pintype "output"))
      (node (ref "X-SOUTH") (pin "92") (pinfunction "92_92") (pintype "bidirectional"))
    )
    (net (code "199") (name "S27_N") (class "Default")
      (node (ref "SENSOR") (pin "A11") (pinfunction "OUT9_N_A11") (pintype "output"))
      (node (ref "X-SOUTH") (pin "95") (pinfunction "95_95") (pintype "bidirectional"))
    )
    (net (code "200") (name "S27_P") (class "Default")
      (node (ref "SENSOR") (pin "A12") (pinfunction "OUT9_P_A12") (pintype "output"))
      (node (ref "X-SOUTH") (pin "93") (pinfunction "93_93") (pintype "bidirectional"))
    )
    (net (code "201") (name "S28_N") (class "Default")
      (node (ref "SENSOR") (pin "C11") (pinfunction "OUT11_N_C11") (pintype "output"))
      (node (ref "X-SOUTH") (pin "100") (pinfunction "100_100") (pintype "bidirectional"))
    )
    (net (code "202") (name "S28_P") (class "Default")
      (node (ref "SENSOR") (pin "C12") (pinfunction "OUT11_P_C12") (pintype "output"))
      (node (ref "X-SOUTH") (pin "98") (pinfunction "98_98") (pintype "bidirectional"))
    )
    (net (code "203") (name "S29_N") (class "Default")
      (node (ref "SENSOR") (pin "B10") (pinfunction "OUT8_N_B10") (pintype "output"))
      (node (ref "X-SOUTH") (pin "101") (pinfunction "101_101") (pintype "bidirectional"))
    )
    (net (code "204") (name "S29_P") (class "Default")
      (node (ref "SENSOR") (pin "B11") (pinfunction "OUT8_P_B11") (pintype "output"))
      (node (ref "X-SOUTH") (pin "99") (pinfunction "99_99") (pintype "bidirectional"))
    )
    (net (code "205") (name "S30_N") (class "Default")
      (node (ref "SENSOR") (pin "C9") (pinfunction "OUT7_N_C9") (pintype "output"))
      (node (ref "X-SOUTH") (pin "106") (pinfunction "106_106") (pintype "bidirectional"))
    )
    (net (code "206") (name "S30_P") (class "Default")
      (node (ref "SENSOR") (pin "C10") (pinfunction "OUT7_P_C10") (pintype "output"))
      (node (ref "X-SOUTH") (pin "104") (pinfunction "104_104") (pintype "bidirectional"))
    )
    (net (code "207") (name "S31_N") (class "Default")
      (node (ref "SENSOR") (pin "B8") (pinfunction "OUT5_N_B8") (pintype "output"))
      (node (ref "X-SOUTH") (pin "107") (pinfunction "107_107") (pintype "bidirectional"))
    )
    (net (code "208") (name "S31_P") (class "Default")
      (node (ref "SENSOR") (pin "B9") (pinfunction "OUT5_P_B9") (pintype "output"))
      (node (ref "X-SOUTH") (pin "105") (pinfunction "105_105") (pintype "bidirectional"))
    )
    (net (code "209") (name "S32_N") (class "Default")
      (node (ref "SENSOR") (pin "D9") (pinfunction "OUT6_N_D9") (pintype "output"))
      (node (ref "X-SOUTH") (pin "112") (pinfunction "112_112") (pintype "bidirectional"))
    )
    (net (code "210") (name "S32_P") (class "Default")
      (node (ref "SENSOR") (pin "D10") (pinfunction "OUT6_P_D10") (pintype "output"))
      (node (ref "X-SOUTH") (pin "110") (pinfunction "110_110") (pintype "bidirectional"))
    )
    (net (code "211") (name "S33_N") (class "Default")
      (node (ref "SENSOR") (pin "A7") (pinfunction "OUT2_N_A7") (pintype "output"))
      (node (ref "X-SOUTH") (pin "113") (pinfunction "113_113") (pintype "bidirectional"))
    )
    (net (code "212") (name "S33_P") (class "Default")
      (node (ref "SENSOR") (pin "A8") (pinfunction "OUT2_P_A8") (pintype "output"))
      (node (ref "X-SOUTH") (pin "111") (pinfunction "111_111") (pintype "bidirectional"))
    )
    (net (code "213") (name "S34_N") (class "Default")
      (node (ref "SENSOR") (pin "C7") (pinfunction "OUT4_N_C7") (pintype "output"))
      (node (ref "X-SOUTH") (pin "118") (pinfunction "118_118") (pintype "bidirectional"))
    )
    (net (code "214") (name "S34_P") (class "Default")
      (node (ref "SENSOR") (pin "C8") (pinfunction "OUT4_P_C8") (pintype "output"))
      (node (ref "X-SOUTH") (pin "116") (pinfunction "116_116") (pintype "bidirectional"))
    )
    (net (code "215") (name "S35_N") (class "Default")
      (node (ref "SENSOR") (pin "B6") (pinfunction "OUT1_N_B6") (pintype "output"))
      (node (ref "X-SOUTH") (pin "119") (pinfunction "119_119") (pintype "bidirectional"))
    )
    (net (code "216") (name "S35_P") (class "Default")
      (node (ref "SENSOR") (pin "B7") (pinfunction "OUT1_P_B7") (pintype "output"))
      (node (ref "X-SOUTH") (pin "117") (pinfunction "117_117") (pintype "bidirectional"))
    )
    (net (code "217") (name "S36_N") (class "Default")
      (node (ref "SENSOR") (pin "D7") (pinfunction "OUT3_N_D7") (pintype "output"))
      (node (ref "X-SOUTH") (pin "124") (pinfunction "124_124") (pintype "bidirectional"))
    )
    (net (code "218") (name "S36_P") (class "Default")
      (node (ref "SENSOR") (pin "D8") (pinfunction "OUT3_P_D8") (pintype "output"))
      (node (ref "X-SOUTH") (pin "122") (pinfunction "122_122") (pintype "bidirectional"))
    )
    (net (code "219") (name "S37_N") (class "Default")
      (node (ref "SENSOR") (pin "A5") (pinfunction "OUTCTR_N_A5") (pintype "output"))
      (node (ref "X-SOUTH") (pin "125") (pinfunction "125_125") (pintype "bidirectional"))
    )
    (net (code "220") (name "S37_P") (class "Default")
      (node (ref "SENSOR") (pin "A6") (pinfunction "OUTCTR_P_A6") (pintype "output"))
      (node (ref "X-SOUTH") (pin "123") (pinfunction "123_123") (pintype "bidirectional"))
    )
    (net (code "221") (name "S38_N") (class "Default")
      (node (ref "X-SOUTH") (pin "130") (pinfunction "130_130") (pintype "bidirectional"))
    )
    (net (code "222") (name "S38_P") (class "Default")
      (node (ref "X-SOUTH") (pin "128") (pinfunction "128_128") (pintype "bidirectional"))
    )
    (net (code "223") (name "S39_N") (class "Default")
      (node (ref "U3") (pin "6") (pinfunction "EN_6") (pintype "input"))
      (node (ref "X-SOUTH") (pin "131") (pinfunction "131_131") (pintype "bidirectional"))
    )
    (net (code "224") (name "S39_P") (class "Default")
      (node (ref "X-SOUTH") (pin "129") (pinfunction "129_129") (pintype "bidirectional"))
    )
    (net (code "225") (name "SPI_CLK") (class "Default")
      (node (ref "SENSOR") (pin "H29") (pinfunction "SPI_CLK_H29") (pintype "input"))
      (node (ref "U4") (pin "9") (pinfunction "B4_9") (pintype "bidirectional"))
    )
    (net (code "226") (name "SPI_EN") (class "Default")
      (node (ref "SENSOR") (pin "F28") (pinfunction "SPI_EN_F28") (pintype "input"))
      (node (ref "U4") (pin "12") (pinfunction "B1_12") (pintype "bidirectional"))
    )
    (net (code "227") (name "SPI_IN") (class "Default")
      (node (ref "SENSOR") (pin "E28") (pinfunction "SPI_IN_E28") (pintype "input"))
      (node (ref "U4") (pin "10") (pinfunction "B3_10") (pintype "bidirectional"))
    )
    (net (code "228") (name "SPI_OUT") (class "Default")
      (node (ref "SENSOR") (pin "G28") (pinfunction "SPI_OUT_G28") (pintype "output"))
      (node (ref "U4") (pin "11") (pinfunction "B2_11") (pintype "bidirectional"))
    )
    (net (code "229") (name "SYS_RES_N") (class "Default")
      (node (ref "SENSOR") (pin "F30") (pinfunction "SYS_RES_N_F30") (pintype "input"))
      (node (ref "U5") (pin "10") (pinfunction "B3_10") (pintype "bidirectional"))
    )
    (net (code "230") (name "S_CHK_EN") (class "Default")
      (node (ref "X-SOUTH") (pin "8") (pinfunction "8_8") (pintype "bidirectional"))
    )
    (net (code "231") (name "S_CHK_V") (class "Default")
      (node (ref "C5") (pin "1") (pinfunction "1_1") (pintype "passive"))
      (node (ref "C6") (pin "1") (pinfunction "1_1") (pintype "passive"))
      (node (ref "C7") (pin "1") (pinfunction "1_1") (pintype "passive"))
      (node (ref "R20") (pin "1") (pinfunction "1_1") (pintype "passive"))
      (node (ref "TP3") (pin "TP") (pinfunction "TP_TP") (pintype "input"))
      (node (ref "USE") (pin "8") (pinfunction "VDD_8") (pintype "power_in"))
      (node (ref "USS") (pin "8") (pinfunction "VDD_8") (pintype "power_in"))
      (node (ref "USW") (pin "8") (pinfunction "VDD_8") (pintype "power_in"))
      (node (ref "X-SOUTH") (pin "10") (pinfunction "10_10") (pintype "bidirectional"))
    )
    (net (code "232") (name "S_I2C_EN") (class "Default")
      (node (ref "X-SOUTH") (pin "137") (pinfunction "137_137") (pintype "bidirectional"))
    )
    (net (code "233") (name "S_I2C_V") (class "Default")
      (node (ref "U7") (pin "8") (pinfunction "VCC_8") (pintype "power_in"))
      (node (ref "X-SOUTH") (pin "135") (pinfunction "135_135") (pintype "bidirectional"))
    )
    (net (code "234") (name "S_REF") (class "Default")
      (node (ref "R20") (pin "2") (pinfunction "2_2") (pintype "passive"))
      (node (ref "TP4") (pin "TP") (pinfunction "TP_TP") (pintype "input"))
      (node (ref "U2") (pin "1") (pinfunction "CATHODE_1") (pintype "output"))
      (node (ref "U2") (pin "3") (pinfunction "REF_3") (pintype "input"))
      (node (ref "USE") (pin "2") (pinfunction "VINA-_2") (pintype "input"))
      (node (ref "USE") (pin "5") (pinfunction "VINB+_5") (pintype "input"))
      (node (ref "USS") (pin "2") (pinfunction "VINA-_2") (pintype "input"))
      (node (ref "USS") (pin "5") (pinfunction "VINB+_5") (pintype "input"))
      (node (ref "USW") (pin "2") (pinfunction "VINA-_2") (pintype "input"))
      (node (ref "USW") (pin "5") (pinfunction "VINB+_5") (pintype "input"))
    )
    (net (code "235") (name "S_SCK") (class "Default")
      (node (ref "X-SOUTH") (pin "144") (pinfunction "144_144") (pintype "bidirectional"))
    )
    (net (code "236") (name "S_SCL") (class "Default")
      (node (ref "U7") (pin "2") (pinfunction "SCL_2") (pintype "input"))
      (node (ref "X-SOUTH") (pin "143") (pinfunction "143_143") (pintype "bidirectional"))
    )
    (net (code "237") (name "S_SDA") (class "Default")
      (node (ref "U7") (pin "1") (pinfunction "SDA_1") (pintype "bidirectional"))
      (node (ref "X-SOUTH") (pin "141") (pinfunction "141_141") (pintype "bidirectional"))
    )
    (net (code "238") (name "S_SDI") (class "Default")
      (node (ref "X-SOUTH") (pin "140") (pinfunction "140_140") (pintype "bidirectional"))
    )
    (net (code "239") (name "S_SDO") (class "Default")
      (node (ref "X-SOUTH") (pin "142") (pinfunction "142_142") (pintype "bidirectional"))
    )
    (net (code "240") (name "S_SPI_EN") (class "Default")
      (node (ref "X-SOUTH") (pin "136") (pinfunction "136_136") (pintype "bidirectional"))
    )
    (net (code "241") (name "S_SPI_V") (class "Default")
      (node (ref "X-SOUTH") (pin "134") (pinfunction "134_134") (pintype "bidirectional"))
    )
    (net (code "242") (name "S_VE") (class "Default")
      (node (ref "X-SOUTH") (pin "13") (pinfunction "13_13") (pintype "bidirectional"))
      (node (ref "X-SOUTH") (pin "19") (pinfunction "19_19") (pintype "bidirectional"))
      (node (ref "X-SOUTH") (pin "25") (pinfunction "25_25") (pintype "bidirectional"))
      (node (ref "X-SOUTH") (pin "31") (pinfunction "31_31") (pintype "bidirectional"))
      (node (ref "X-SOUTH") (pin "37") (pinfunction "37_37") (pintype "bidirectional"))
    )
    (net (code "243") (name "S_VE_CV") (class "Default")
      (node (ref "C11") (pin "1") (pinfunction "1_1") (pintype "passive"))
      (node (ref "R10") (pin "1") (pinfunction "1_1") (pintype "passive"))
      (node (ref "X-SOUTH") (pin "2") (pinfunction "2_2") (pintype "bidirectional"))
    )
    (net (code "244") (name "S_VE_OV") (class "Default")
      (node (ref "USE") (pin "7") (pinfunction "OUTB_7") (pintype "output"))
      (node (ref "X-SOUTH") (pin "1") (pinfunction "1_1") (pintype "bidirectional"))
    )
    (net (code "245") (name "S_VE_UV") (class "Default")
      (node (ref "USE") (pin "1") (pinfunction "OUTA_1") (pintype "output"))
      (node (ref "X-SOUTH") (pin "7") (pinfunction "7_7") (pintype "bidirectional"))
    )
    (net (code "246") (name "S_VS") (class "Default")
      (node (ref "C45") (pin "1") (pinfunction "1_1") (pintype "passive"))
      (node (ref "C46") (pin "1") (pinfunction "1_1") (pintype "passive"))
      (node (ref "C47") (pin "1") (pinfunction "1_1") (pintype "passive"))
      (node (ref "C48") (pin "1") (pinfunction "1_1") (pintype "passive"))
      (node (ref "C49") (pin "1") (pinfunction "1_1") (pintype "passive"))
      (node (ref "C72") (pin "1") (pinfunction "1_1") (pintype "passive"))
      (node (ref "C73") (pin "1") (pinfunction "1_1") (pintype "passive"))
      (node (ref "C74") (pin "1") (pinfunction "1_1") (pintype "passive"))
      (node (ref "C81") (pin "1") (pinfunction "1_1") (pintype "passive"))
      (node (ref "C82") (pin "1") (pinfunction "1_1") (pintype "passive"))
      (node (ref "C83") (pin "1") (pinfunction "1_1") (pintype "passive"))
      (node (ref "SENSOR") (pin "A30") (pinfunction "VDD_PIX_A30") (pintype "power_in"))
      (node (ref "SENSOR") (pin "D28") (pinfunction "VDD_PIX_D28") (pintype "power_in"))
      (node (ref "SENSOR") (pin "D30") (pinfunction "VDD_PIX_D30") (pintype "power_in"))
      (node (ref "SENSOR") (pin "G1") (pinfunction "VDD_PIX_G1") (pintype "power_in"))
      (node (ref "SENSOR") (pin "H28") (pinfunction "VDD_PIX_H28") (pintype "power_in"))
      (node (ref "TP6") (pin "TP") (pinfunction "TP_TP") (pintype "input"))
      (node (ref "X-SOUTH") (pin "49") (pinfunction "49_49") (pintype "bidirectional"))
      (node (ref "X-SOUTH") (pin "55") (pinfunction "55_55") (pintype "bidirectional"))
      (node (ref "X-SOUTH") (pin "61") (pinfunction "61_61") (pintype "bidirectional"))
      (node (ref "X-SOUTH") (pin "67") (pinfunction "67_67") (pintype "bidirectional"))
      (node (ref "X-SOUTH") (pin "73") (pinfunction "73_73") (pintype "bidirectional"))
      (node (ref "X-SOUTH") (pin "79") (pinfunction "79_79") (pintype "bidirectional"))
      (node (ref "X-SOUTH") (pin "85") (pinfunction "85_85") (pintype "bidirectional"))
      (node (ref "X-SOUTH") (pin "91") (pinfunction "91_91") (pintype "bidirectional"))
      (node (ref "X-SOUTH") (pin "97") (pinfunction "97_97") (pintype "bidirectional"))
    )
    (net (code "247") (name "S_VS_CV") (class "Default")
      (node (ref "C12") (pin "1") (pinfunction "1_1") (pintype "passive"))
      (node (ref "R13") (pin "1") (pinfunction "1_1") (pintype "passive"))
      (node (ref "X-SOUTH") (pin "4") (pinfunction "4_4") (pintype "bidirectional"))
    )
    (net (code "248") (name "S_VS_OV") (class "Default")
      (node (ref "USS") (pin "7") (pinfunction "OUTB_7") (pintype "output"))
      (node (ref "X-SOUTH") (pin "3") (pinfunction "3_3") (pintype "bidirectional"))
    )
    (net (code "249") (name "S_VS_UV") (class "Default")
      (node (ref "USS") (pin "1") (pinfunction "OUTA_1") (pintype "output"))
      (node (ref "X-SOUTH") (pin "9") (pinfunction "9_9") (pintype "bidirectional"))
    )
    (net (code "250") (name "S_VW") (class "Default")
      (node (ref "C90") (pin "1") (pinfunction "1_1") (pintype "passive"))
      (node (ref "U3") (pin "1") (pinfunction "BIAS_1") (pintype "power_in"))
      (node (ref "U3") (pin "3") (pinfunction "IN_3") (pintype "power_in"))
      (node (ref "X-SOUTH") (pin "109") (pinfunction "109_109") (pintype "bidirectional"))
      (node (ref "X-SOUTH") (pin "115") (pinfunction "115_115") (pintype "bidirectional"))
      (node (ref "X-SOUTH") (pin "121") (pinfunction "121_121") (pintype "bidirectional"))
      (node (ref "X-SOUTH") (pin "127") (pinfunction "127_127") (pintype "bidirectional"))
      (node (ref "X-SOUTH") (pin "133") (pinfunction "133_133") (pintype "bidirectional"))
    )
    (net (code "251") (name "S_VW_CV") (class "Default")
      (node (ref "C13") (pin "1") (pinfunction "1_1") (pintype "passive"))
      (node (ref "R16") (pin "1") (pinfunction "1_1") (pintype "passive"))
      (node (ref "X-SOUTH") (pin "6") (pinfunction "6_6") (pintype "bidirectional"))
    )
    (net (code "252") (name "S_VW_OV") (class "Default")
      (node (ref "USW") (pin "7") (pinfunction "OUTB_7") (pintype "output"))
      (node (ref "X-SOUTH") (pin "5") (pinfunction "5_5") (pintype "bidirectional"))
    )
    (net (code "253") (name "S_VW_UV") (class "Default")
      (node (ref "USW") (pin "1") (pinfunction "OUTA_1") (pintype "output"))
      (node (ref "X-SOUTH") (pin "11") (pinfunction "11_11") (pintype "bidirectional"))
    )
    (net (code "254") (name "TDIG1") (class "Default")
      (node (ref "SENSOR") (pin "G27") (pinfunction "TDIG1_G27") (pintype "output"))
      (node (ref "U5") (pin "9") (pinfunction "B4_9") (pintype "bidirectional"))
    )
    (net (code "255") (name "TDIG2") (class "Default")
      (node (ref "SENSOR") (pin "G26") (pinfunction "TDIG2_G26") (pintype "output"))
      (node (ref "U6") (pin "11") (pinfunction "B2_11") (pintype "bidirectional"))
    )
    (net (code "256") (name "T_EXP1") (class "Default")
      (node (ref "SENSOR") (pin "H30") (pinfunction "T_EXP1_H30") (pintype "input"))
      (node (ref "U5") (pin "12") (pinfunction "B1_12") (pintype "bidirectional"))
    )
    (net (code "257") (name "T_EXP2") (class "Default")
      (node (ref "SENSOR") (pin "E29") (pinfunction "T_EXP2_E29") (pintype "input"))
      (node (ref "U6") (pin "10") (pinfunction "B3_10") (pintype "bidirectional"))
    )
    (net (code "258") (name "VRAMP1") (class "Default")
      (node (ref "C16") (pin "1") (pinfunction "1_1") (pintype "passive"))
      (node (ref "R23") (pin "1") (pinfunction "1_1") (pintype "passive"))
      (node (ref "SENSOR") (pin "G29") (pinfunction "VRAMP1_G29") (pintype "bidirectional"))
    )
    (net (code "259") (name "VRAMP2") (class "Default")
      (node (ref "C17") (pin "1") (pinfunction "1_1") (pintype "passive"))
      (node (ref "R23") (pin "2") (pinfunction "2_2") (pintype "passive"))
      (node (ref "SENSOR") (pin "F29") (pinfunction "VRAMP2_F29") (pintype "bidirectional"))
    )
    (net (code "260") (name "VTREF") (class "Default")
      (node (ref "C65") (pin "1") (pinfunction "1_1") (pintype "passive"))
      (node (ref "C91") (pin "2") (pinfunction "2_2") (pintype "passive"))
      (node (ref "R21") (pin "2") (pinfunction "2_2") (pintype "passive"))
      (node (ref "R24") (pin "1") (pinfunction "1_1") (pintype "passive"))
      (node (ref "SENSOR") (pin "B2") (pinfunction "VTREF_B2") (pintype "bidirectional"))
      (node (ref "U3") (pin "4") (pinfunction "OUT_4") (pintype "power_in"))
    )
    (net (code "261") (name "VTSIG") (class "Default")
      (node (ref "C66") (pin "1") (pinfunction "1_1") (pintype "passive"))
      (node (ref "R24") (pin "2") (pinfunction "2_2") (pintype "passive"))
      (node (ref "SENSOR") (pin "C2") (pinfunction "VTSIG_C2") (pintype "bidirectional"))
    )
    (net (code "262") (name "unconnected-(U1-NC-Pad2)") (class "Default")
      (node (ref "U1") (pin "2") (pinfunction "NC_2") (pintype "no_connect"))
    )
    (net (code "263") (name "unconnected-(U1-NC-Pad4)") (class "Default")
      (node (ref "U1") (pin "4") (pinfunction "NC_4") (pintype "no_connect"))
    )
    (net (code "264") (name "unconnected-(U1-NC-Pad5)") (class "Default")
      (node (ref "U1") (pin "5") (pinfunction "NC_5") (pintype "no_connect"))
    )
    (net (code "265") (name "unconnected-(U2-NC-Pad2)") (class "Default")
      (node (ref "U2") (pin "2") (pinfunction "NC_2") (pintype "no_connect"))
    )
    (net (code "266") (name "unconnected-(U2-NC-Pad4)") (class "Default")
      (node (ref "U2") (pin "4") (pinfunction "NC_4") (pintype "no_connect"))
    )
    (net (code "267") (name "unconnected-(U2-NC-Pad5)") (class "Default")
      (node (ref "U2") (pin "5") (pinfunction "NC_5") (pintype "no_connect"))
    )
    (net (code "268") (name "unconnected-(U7-OS-Pad3)") (class "Default")
      (node (ref "U7") (pin "3") (pinfunction "OS_3") (pintype "output"))
    )
    (net (code "269") (name "unconnected-(X-NORTH-PadM1)") (class "Default")
      (node (ref "X-NORTH") (pin "M1") (pinfunction "M1_M1") (pintype "bidirectional"))
    )
    (net (code "270") (name "unconnected-(X-NORTH-PadM2)") (class "Default")
      (node (ref "X-NORTH") (pin "M2") (pinfunction "M2_M2") (pintype "bidirectional"))
    )
    (net (code "271") (name "unconnected-(X-SOUTH-PadM1)") (class "Default")
      (node (ref "X-SOUTH") (pin "M1") (pinfunction "M1_M1") (pintype "bidirectional"))
    )
    (net (code "272") (name "unconnected-(X-SOUTH-PadM2)") (class "Default")
      (node (ref "X-SOUTH") (pin "M2") (pinfunction "M2_M2") (pintype "bidirectional"))
    )
  )
)
